# Smart_Cube.net
KiCad netlist of a schematic drawn in Altium Designer
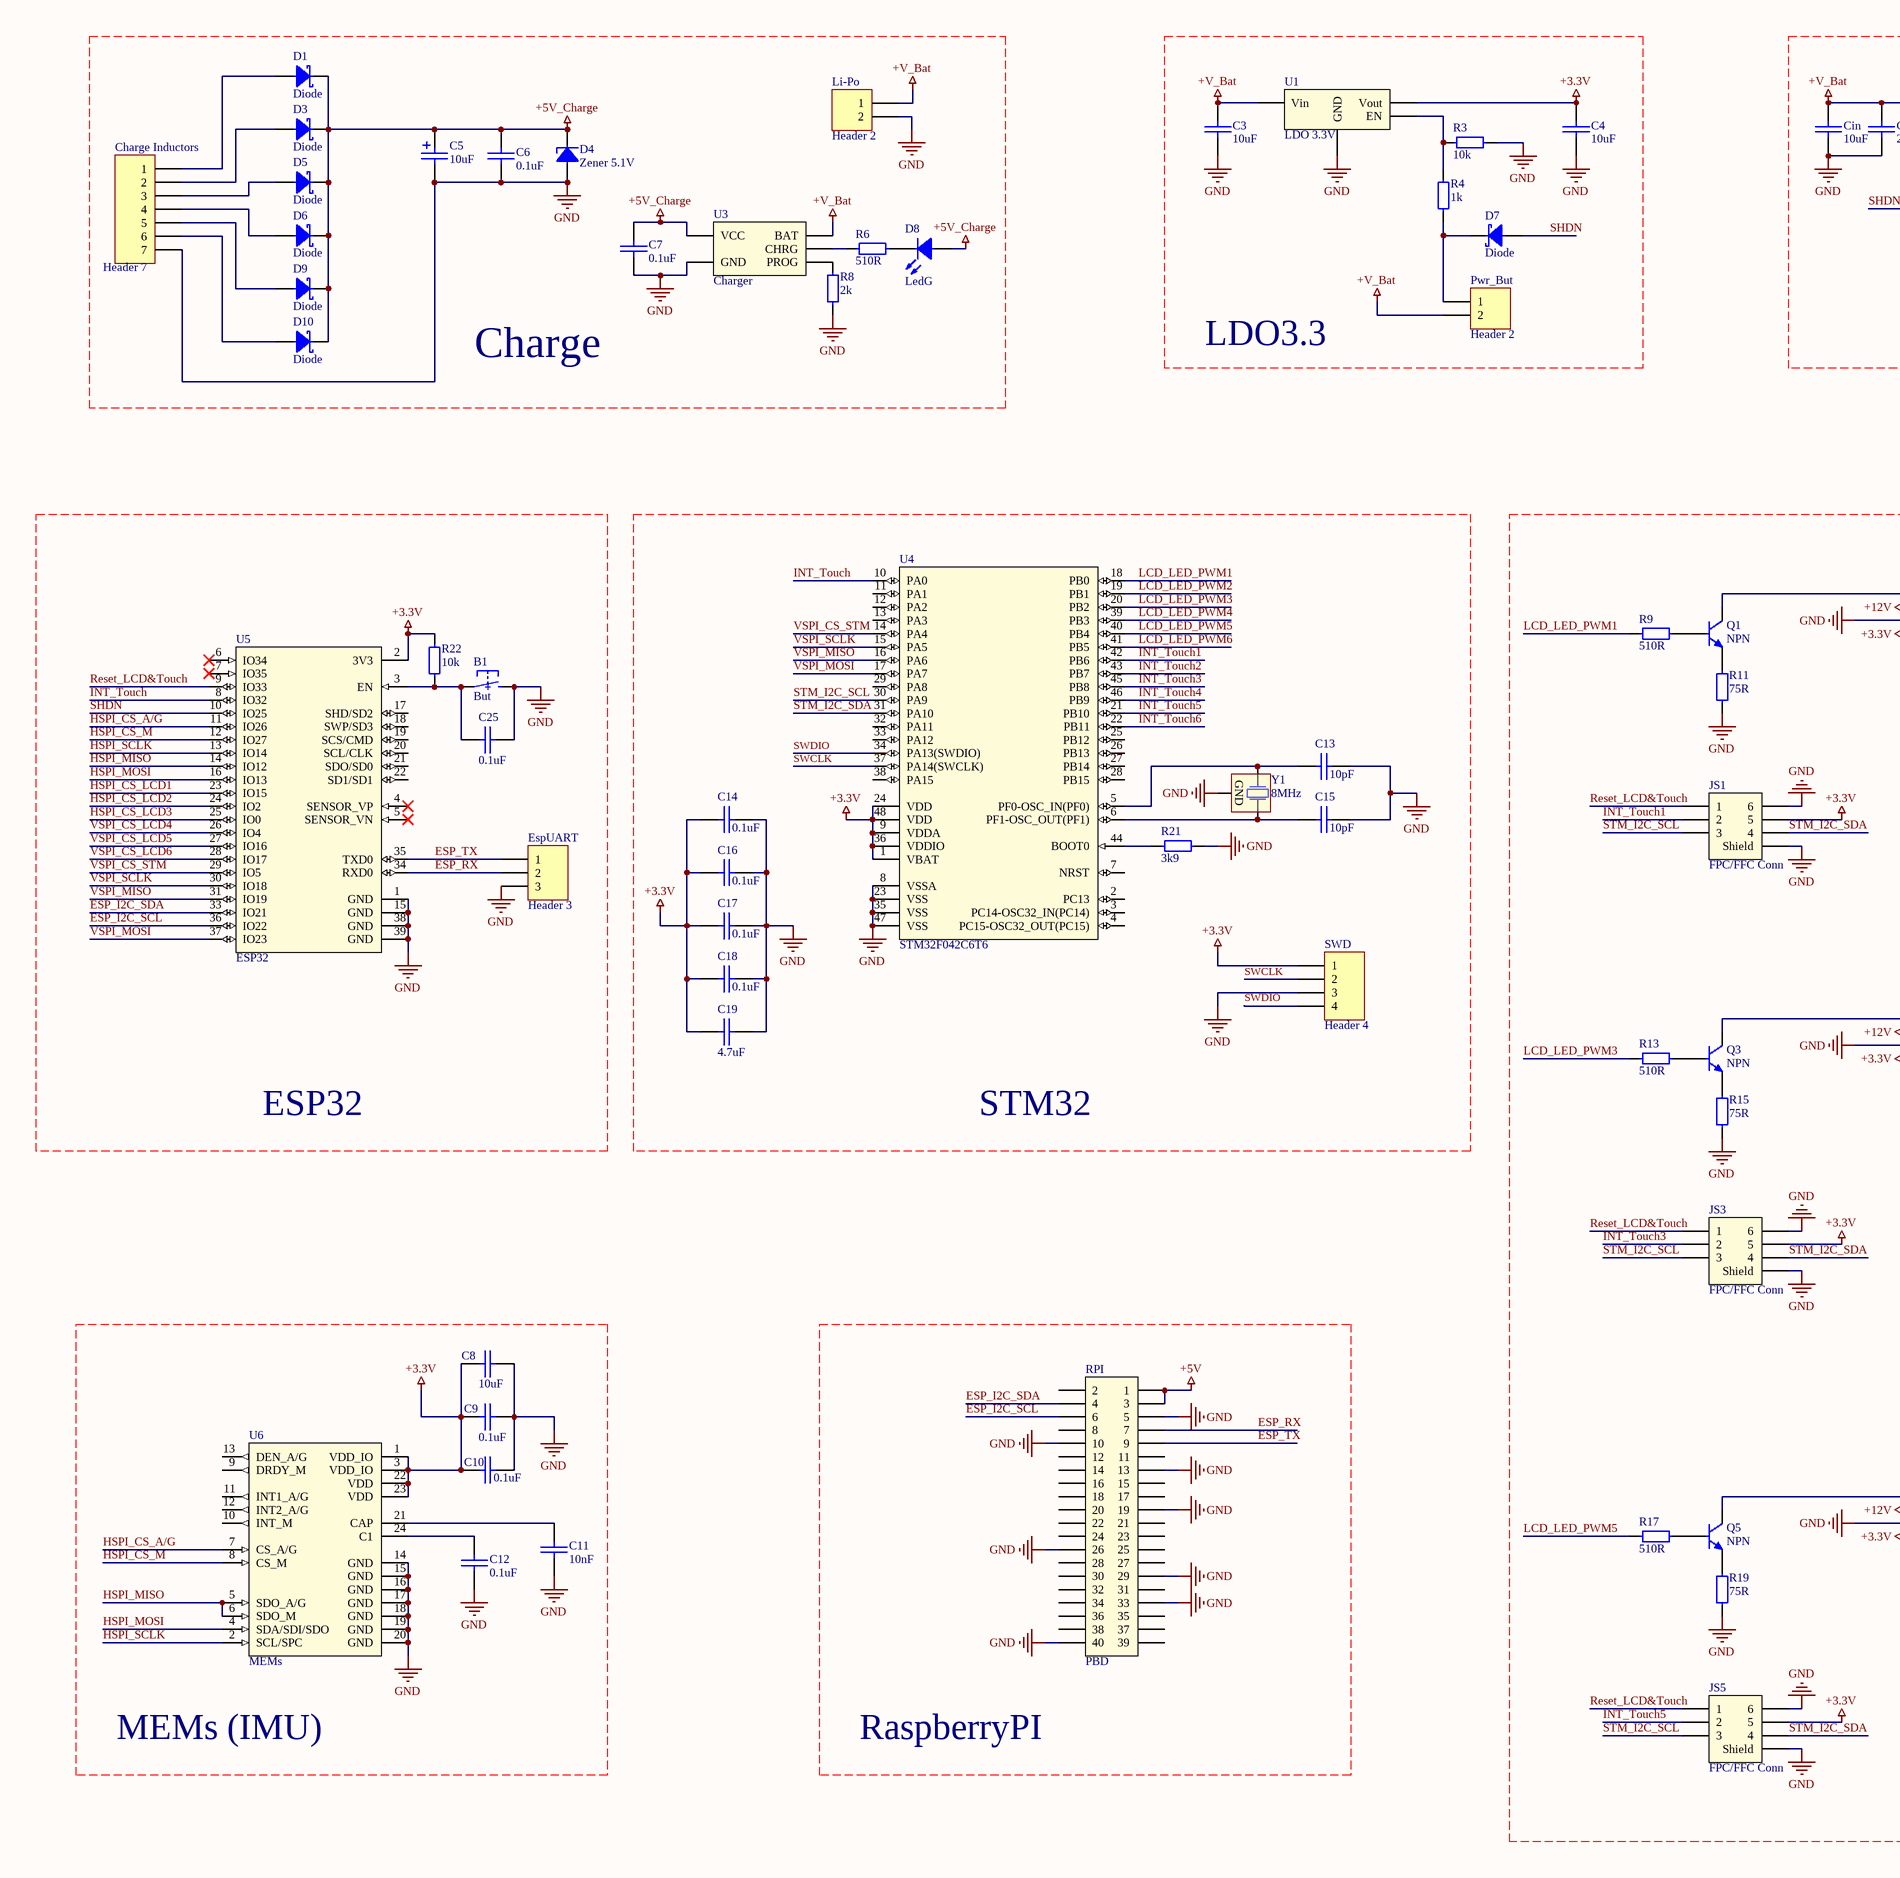
[diagram p0: Smart_Cube.SchDoc, left]
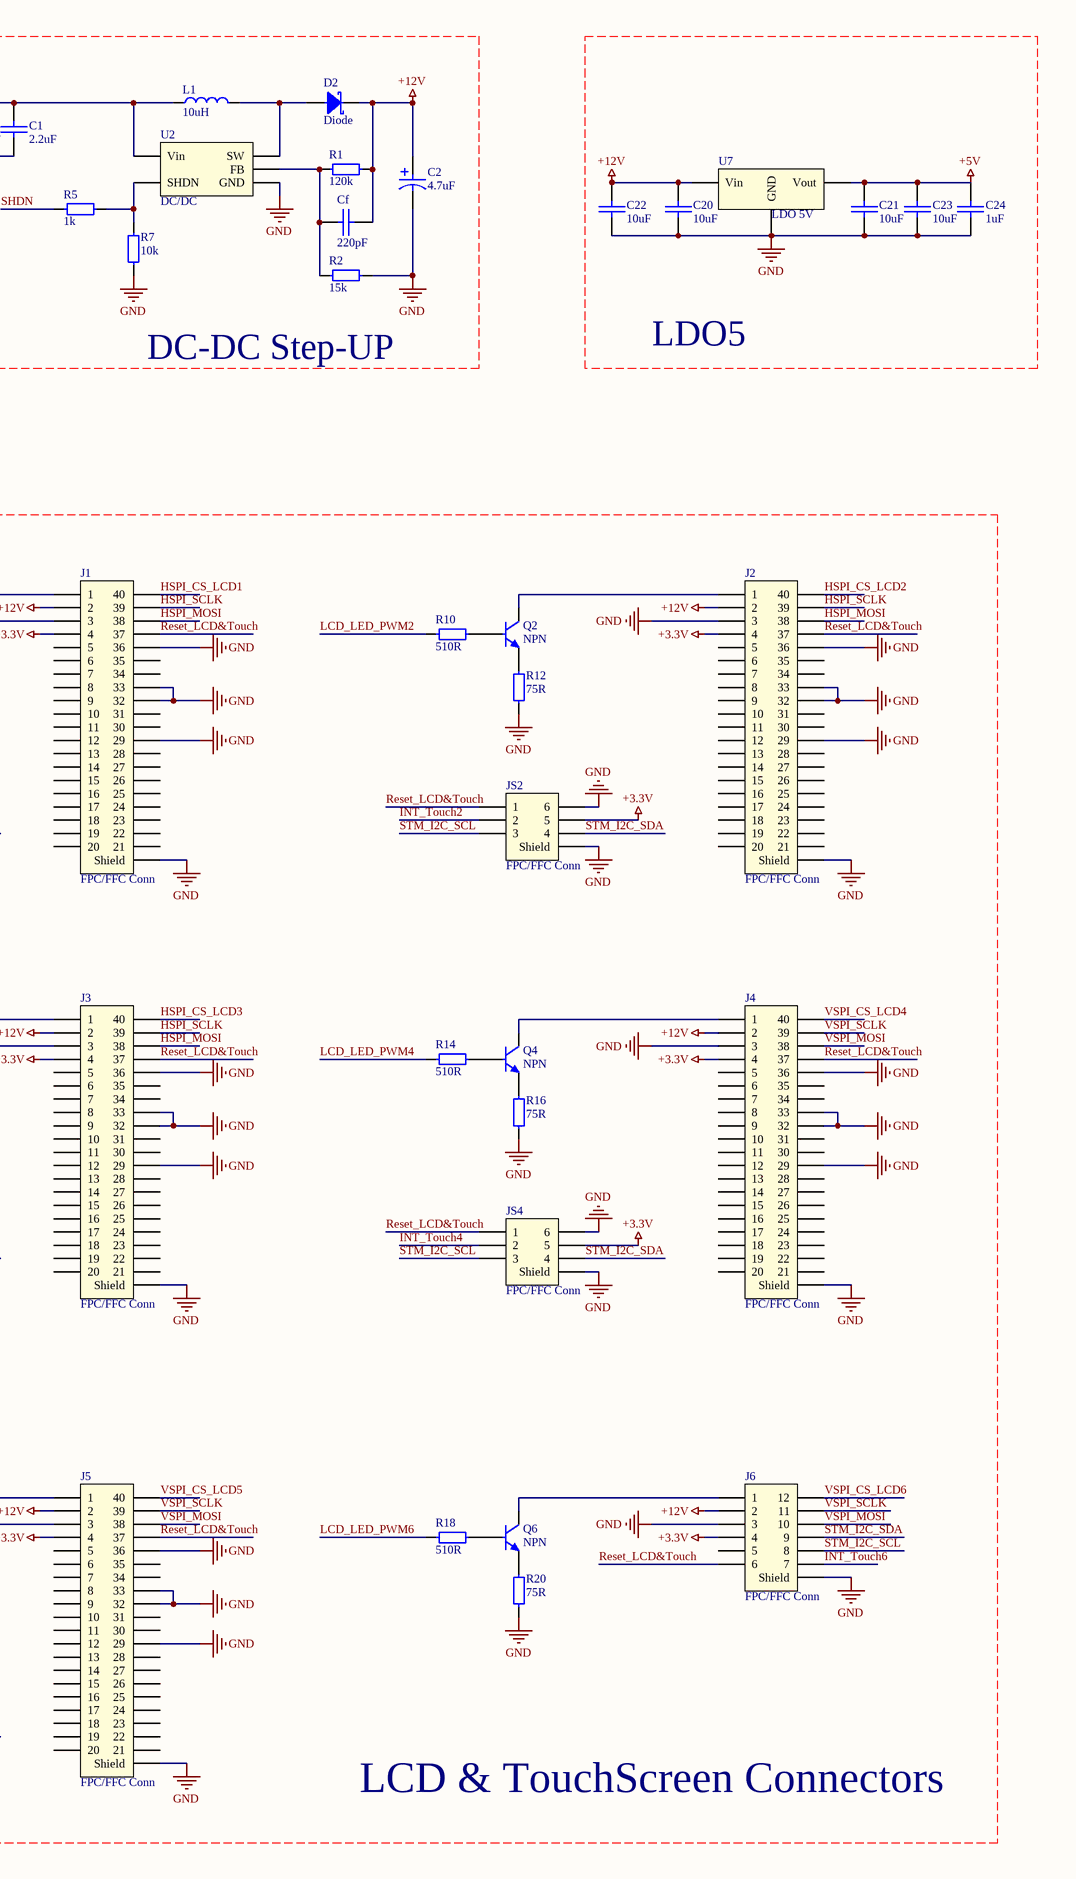
[diagram p1: Smart_Cube.SchDoc, right]

(export (version "E")
  (design (tool "Eeschema 10.0.6"))
  (components
    (comp (ref "B1")
      (value "But")
      (footprint "BUTTON 4x3")
      (description "Button 2 Conn SMD")
      (fields
        (field (name "PART NUMBER") "L-KLS7-TS3608-5.0-180")
        (field (name "MANUFACTURER") "KLS electronic co ltd")
      )
      (libsource (lib "Karen_Components") (part "Button 2 Conn"))
    )
    (comp (ref "C1")
      (value "2.2uF")
      (footprint "0603 Capicator")
      (description "2.2uF X5R 10V 10% 0603")
      (fields
        (field (name "MANUFACTURER") "Murata Manufacturing")
        (field (name "PART NUMBER") "GRM188R61A225KE34D")
      )
      (libsource (lib "Karen_Components") (part "Cap 2.2uF (0603)"))
    )
    (comp (ref "C2")
      (value "4.7uF")
      (footprint "Bar Cap 4x5.4")
      (description "ECAP SMD,  35V, 105°C")
      (fields (field (name "PART NUMBER") "B41121A7475M000") (field (name "MANUFACTURER") "Epcos"))
      (libsource (lib "Karen_Components") (part "Cap Pol 4.7uF"))
    )
    (comp (ref "C3")
      (value "10uF")
      (footprint "0603 Capicator")
      (description "10uF X5R 25V 20% 0603")
      (fields
        (field (name "MANUFACTURER") "Murata Manufacturing")
        (field (name "PART NUMBER") "GRM188R61E106M")
      )
      (libsource (lib "Karen_Components") (part "Cap 10uF (0603)"))
    )
    (comp (ref "C4")
      (value "10uF")
      (footprint "0603 Capicator")
      (description "10uF X5R 25V 20% 0603")
      (fields
        (field (name "MANUFACTURER") "Murata Manufacturing")
        (field (name "PART NUMBER") "GRM188R61E106M")
      )
      (libsource (lib "Karen_Components") (part "Cap 10uF (0603)"))
    )
    (comp (ref "C5")
      (value "10uF")
      (footprint "TANTAL_A_CASE")
      (description "TECAP, 10uF, 16V, case A, 10%")
      (fields (field (name "PART NUMBER") "373033076") (field (name "MANUFACTURER") "China"))
      (libsource (lib "Karen_Components") (part "Cap Tantal 10uF (SMDA)"))
    )
    (comp (ref "C6")
      (value "0.1uF")
      (footprint "0603 Capicator")
      (description "0.1uF X7R 16V 10% 0603")
      (fields
        (field (name "MANUFACTURER") "Murata Manufacturing")
        (field (name "PART NUMBER") "GRM188R71C104KA01D")
      )
      (libsource (lib "Karen_Components") (part "Cap 0.1uF (0603)"))
    )
    (comp (ref "C7")
      (value "0.1uF")
      (footprint "0603 Capicator")
      (description "0.1uF X7R 16V 10% 0603")
      (fields
        (field (name "MANUFACTURER") "Murata Manufacturing")
        (field (name "PART NUMBER") "GRM188R71C104KA01D")
      )
      (libsource (lib "Karen_Components") (part "Cap 0.1uF (0603)"))
    )
    (comp (ref "C8")
      (value "10uF")
      (footprint "0603 Capicator")
      (description "10uF X5R 25V 20% 0603")
      (fields
        (field (name "MANUFACTURER") "Murata Manufacturing")
        (field (name "PART NUMBER") "GRM188R61E106M")
      )
      (libsource (lib "Karen_Components") (part "Cap 10uF (0603)"))
    )
    (comp (ref "C9")
      (value "0.1uF")
      (footprint "0603 Capicator")
      (description "0.1uF X7R 16V 10% 0603")
      (fields
        (field (name "MANUFACTURER") "Murata Manufacturing")
        (field (name "PART NUMBER") "GRM188R71C104KA01D")
      )
      (libsource (lib "Karen_Components") (part "Cap 0.1uF (0603)"))
    )
    (comp (ref "C10")
      (value "0.1uF")
      (footprint "0603 Capicator")
      (description "0.1uF X7R 16V 10% 0603")
      (fields
        (field (name "MANUFACTURER") "Murata Manufacturing")
        (field (name "PART NUMBER") "GRM188R71C104KA01D")
      )
      (libsource (lib "Karen_Components") (part "Cap 0.1uF (0603)"))
    )
    (comp (ref "C11")
      (value "10nF")
      (footprint "0603 Capicator")
      (description "X7R 10nF 100V 10% 0603")
      (fields
        (field (name "MANUFACTURER") "Murata Manufacturing")
        (field (name "PART NUMBER") "GRM188R72A103KA01D")
      )
      (libsource (lib "Karen_Components") (part "Cap 10nF (0603)"))
    )
    (comp (ref "C12")
      (value "0.1uF")
      (footprint "0603 Capicator")
      (description "0.1uF X7R 16V 10% 0603")
      (fields
        (field (name "MANUFACTURER") "Murata Manufacturing")
        (field (name "PART NUMBER") "GRM188R71C104KA01D")
      )
      (libsource (lib "Karen_Components") (part "Cap 0.1uF (0603)"))
    )
    (comp (ref "C13")
      (value "10pF")
      (footprint "0603 Capicator")
      (description "10pF NP0 50V 5% 0603")
      (fields
        (field (name "MANUFACTURER") "Murata Manufacturing")
        (field (name "PART NUMBER") "GRM1885C1H100JA01D")
      )
      (libsource (lib "Karen_Components") (part "Cap 10pF (0603)"))
    )
    (comp (ref "C14")
      (value "0.1uF")
      (footprint "0603 Capicator")
      (description "0.1uF X7R 16V 10% 0603")
      (fields
        (field (name "MANUFACTURER") "Murata Manufacturing")
        (field (name "PART NUMBER") "GRM188R71C104KA01D")
      )
      (libsource (lib "Karen_Components") (part "Cap 0.1uF (0603)"))
    )
    (comp (ref "C15")
      (value "10pF")
      (footprint "0603 Capicator")
      (description "10pF NP0 50V 5% 0603")
      (fields
        (field (name "MANUFACTURER") "Murata Manufacturing")
        (field (name "PART NUMBER") "GRM1885C1H100JA01D")
      )
      (libsource (lib "Karen_Components") (part "Cap 10pF (0603)"))
    )
    (comp (ref "C16")
      (value "0.1uF")
      (footprint "0603 Capicator")
      (description "0.1uF X7R 16V 10% 0603")
      (fields
        (field (name "MANUFACTURER") "Murata Manufacturing")
        (field (name "PART NUMBER") "GRM188R71C104KA01D")
      )
      (libsource (lib "Karen_Components") (part "Cap 0.1uF (0603)"))
    )
    (comp (ref "C17")
      (value "0.1uF")
      (footprint "0603 Capicator")
      (description "0.1uF X7R 16V 10% 0603")
      (fields
        (field (name "MANUFACTURER") "Murata Manufacturing")
        (field (name "PART NUMBER") "GRM188R71C104KA01D")
      )
      (libsource (lib "Karen_Components") (part "Cap 0.1uF (0603)"))
    )
    (comp (ref "C18")
      (value "0.1uF")
      (footprint "0603 Capicator")
      (description "0.1uF X7R 16V 10% 0603")
      (fields
        (field (name "MANUFACTURER") "Murata Manufacturing")
        (field (name "PART NUMBER") "GRM188R71C104KA01D")
      )
      (libsource (lib "Karen_Components") (part "Cap 0.1uF (0603)"))
    )
    (comp (ref "C19")
      (value "4.7uF")
      (footprint "0603 Capicator")
      (description "4.7uF X5R 6.3V 10% 0603")
      (fields
        (field (name "MANUFACTURER") "Murata Manufacturing")
        (field (name "PART NUMBER") "GRM188R60J475KE19D")
      )
      (libsource (lib "Karen_Components") (part "Cap 4.7uF (0603)"))
    )
    (comp (ref "C20")
      (value "10uF")
      (footprint "0603 Capicator")
      (description "10uF X5R 25V 20% 0603")
      (fields
        (field (name "MANUFACTURER") "Murata Manufacturing")
        (field (name "PART NUMBER") "GRM188R61E106M")
      )
      (libsource (lib "Karen_Components") (part "Cap 10uF (0603)"))
    )
    (comp (ref "C21")
      (value "10uF")
      (footprint "0603 Capicator")
      (description "10uF X5R 25V 20% 0603")
      (fields
        (field (name "MANUFACTURER") "Murata Manufacturing")
        (field (name "PART NUMBER") "GRM188R61E106M")
      )
      (libsource (lib "Karen_Components") (part "Cap 10uF (0603)"))
    )
    (comp (ref "C22")
      (value "10uF")
      (footprint "0603 Capicator")
      (description "10uF X5R 25V 20% 0603")
      (fields
        (field (name "MANUFACTURER") "Murata Manufacturing")
        (field (name "PART NUMBER") "GRM188R61E106M")
      )
      (libsource (lib "Karen_Components") (part "Cap 10uF (0603)"))
    )
    (comp (ref "C23")
      (value "10uF")
      (footprint "0603 Capicator")
      (description "10uF X5R 25V 20% 0603")
      (fields
        (field (name "MANUFACTURER") "Murata Manufacturing")
        (field (name "PART NUMBER") "GRM188R61E106M")
      )
      (libsource (lib "Karen_Components") (part "Cap 10uF (0603)"))
    )
    (comp (ref "C24")
      (value "1uF")
      (footprint "0603 Capicator")
      (description "1uF X5R 25V 10% 0603")
      (fields
        (field (name "MANUFACTURER") "Murata Manufacturing")
        (field (name "PART NUMBER") "GRM188R61E105KAADD")
      )
      (libsource (lib "Karen_Components") (part "Cap 1uF (0603)"))
    )
    (comp (ref "C25")
      (value "0.1uF")
      (footprint "0603 Capicator")
      (description "0.1uF X7R 16V 10% 0603")
      (fields
        (field (name "MANUFACTURER") "Murata Manufacturing")
        (field (name "PART NUMBER") "GRM188R71C104KA01D")
      )
      (libsource (lib "Karen_Components") (part "Cap 0.1uF (0603)"))
    )
    (comp (ref "Cf")
      (value "220pF")
      (footprint "0603 Capicator")
      (description "220pF NP0 50V 5% 0603")
      (fields
        (field (name "MANUFACTURER") "Murata Manufacturing")
        (field (name "PART NUMBER") "GRM1885C1H221J")
      )
      (libsource (lib "Karen_Components") (part "Cap 220pF (0603)"))
    )
    (comp (ref "Charge Inductors")
      (value "Header 7")
      (footprint "HDR1X7")
      (description "Header, 7-Pin")
      (fields (field (name "PUBLISHER") "Altium Limited"))
      (libsource (lib "Miscellaneous Connectors") (part "Header 7"))
    )
    (comp (ref "Cin")
      (value "10uF")
      (footprint "0603 Capicator")
      (description "10uF X5R 25V 20% 0603")
      (fields
        (field (name "MANUFACTURER") "Murata Manufacturing")
        (field (name "PART NUMBER") "GRM188R61E106M")
      )
      (libsource (lib "Karen_Components") (part "Cap 10uF (0603)"))
    )
    (comp (ref "D1")
      (value "Diode")
      (footprint "sod-123")
      (description "0.5 A, Low Forward Voltage less than 385 mV, 400 mW Power Dissipation Package")
      (fields (field (name "PART NUMBER") "MBR0520L") (field (name "MANUFACTURER") "ON Semiconductor"))
      (libsource (lib "Karen_Components") (part "Diode Schottky (SOD-123)"))
    )
    (comp (ref "D2")
      (value "Diode")
      (footprint "sod-123")
      (description "0.5 A, Low Forward Voltage less than 385 mV, 400 mW Power Dissipation Package")
      (fields (field (name "PART NUMBER") "MBR0520L") (field (name "MANUFACTURER") "ON Semiconductor"))
      (libsource (lib "Karen_Components") (part "Diode Schottky (SOD-123)"))
    )
    (comp (ref "D3")
      (value "Diode")
      (footprint "sod-123")
      (description "0.5 A, Low Forward Voltage less than 385 mV, 400 mW Power Dissipation Package")
      (fields (field (name "PART NUMBER") "MBR0520L") (field (name "MANUFACTURER") "ON Semiconductor"))
      (libsource (lib "Karen_Components") (part "Diode Schottky (SOD-123)"))
    )
    (comp (ref "D4")
      (value "Zener 5.1V")
      (footprint "sod-323")
      (description "300mW")
      (fields (field (name "PART NUMBER") "BZX384-C5V1,115") (field (name "MANUFACTURER") "Nexperia"))
      (libsource (lib "Karen_Components") (part "Zener Diode 5.1V"))
    )
    (comp (ref "D5")
      (value "Diode")
      (footprint "sod-123")
      (description "0.5 A, Low Forward Voltage less than 385 mV, 400 mW Power Dissipation Package")
      (fields (field (name "PART NUMBER") "MBR0520L") (field (name "MANUFACTURER") "ON Semiconductor"))
      (libsource (lib "Karen_Components") (part "Diode Schottky (SOD-123)"))
    )
    (comp (ref "D6")
      (value "Diode")
      (footprint "sod-123")
      (description "0.5 A, Low Forward Voltage less than 385 mV, 400 mW Power Dissipation Package")
      (fields (field (name "PART NUMBER") "MBR0520L") (field (name "MANUFACTURER") "ON Semiconductor"))
      (libsource (lib "Karen_Components") (part "Diode Schottky (SOD-123)"))
    )
    (comp (ref "D7")
      (value "Diode")
      (footprint "sod-123")
      (description "0.5 A, Low Forward Voltage less than 385 mV, 400 mW Power Dissipation Package")
      (fields (field (name "PART NUMBER") "MBR0520L") (field (name "MANUFACTURER") "ON Semiconductor"))
      (libsource (lib "Karen_Components") (part "Diode Schottky (SOD-123)"))
    )
    (comp (ref "D8")
      (value "LedG")
      (footprint "0805 LED")
      (description "Led Green SMD 1608, 120°, 525nM")
      (fields
        (field (name "PART NUMBER") "TO-1608BC-PG")
        (field (name "MANUFACTURER") "Taiwan Oasis Technology")
      )
      (libsource (lib "Karen_Components") (part "Led Green"))
    )
    (comp (ref "D9")
      (value "Diode")
      (footprint "sod-123")
      (description "0.5 A, Low Forward Voltage less than 385 mV, 400 mW Power Dissipation Package")
      (fields (field (name "PART NUMBER") "MBR0520L") (field (name "MANUFACTURER") "ON Semiconductor"))
      (libsource (lib "Karen_Components") (part "Diode Schottky (SOD-123)"))
    )
    (comp (ref "D10")
      (value "Diode")
      (footprint "sod-123")
      (description "0.5 A, Low Forward Voltage less than 385 mV, 400 mW Power Dissipation Package")
      (fields (field (name "PART NUMBER") "MBR0520L") (field (name "MANUFACTURER") "ON Semiconductor"))
      (libsource (lib "Karen_Components") (part "Diode Schottky (SOD-123)"))
    )
    (comp (ref "EspUART")
      (value "Header 3")
      (footprint "HDR1X3")
      (description "Header, 3-Pin")
      (fields (field (name "PUBLISHER") "Altium Limited"))
      (libsource (lib "Miscellaneous Connectors") (part "Header 3"))
    )
    (comp (ref "J1")
      (value "FPC/FFC Conn")
      (footprint "FH12-40S Vertical")
      (description "Connector to Display's trail")
      (fields
        (field (name "PART NUMBER") "FH12-40S-0.5SVA(54)")
        (field (name "MANUFACTURER") "Hirose Electric")
      )
      (libsource (lib "Karen_Components") (part "Conn40x1 (FH12 Vertical)"))
    )
    (comp (ref "J2")
      (value "FPC/FFC Conn")
      (footprint "FH12-40S Vertical")
      (description "Connector to Display's trail")
      (fields
        (field (name "PART NUMBER") "FH12-40S-0.5SVA(54)")
        (field (name "MANUFACTURER") "Hirose Electric")
      )
      (libsource (lib "Karen_Components") (part "Conn40x1 (FH12 Vertical)"))
    )
    (comp (ref "J3")
      (value "FPC/FFC Conn")
      (footprint "FH12-40S Vertical")
      (description "Connector to Display's trail")
      (fields
        (field (name "PART NUMBER") "FH12-40S-0.5SVA(54)")
        (field (name "MANUFACTURER") "Hirose Electric")
      )
      (libsource (lib "Karen_Components") (part "Conn40x1 (FH12 Vertical)"))
    )
    (comp (ref "J4")
      (value "FPC/FFC Conn")
      (footprint "FH12-40S Vertical")
      (description "Connector to Display's trail")
      (fields
        (field (name "PART NUMBER") "FH12-40S-0.5SVA(54)")
        (field (name "MANUFACTURER") "Hirose Electric")
      )
      (libsource (lib "Karen_Components") (part "Conn40x1 (FH12 Vertical)"))
    )
    (comp (ref "J5")
      (value "FPC/FFC Conn")
      (footprint "FH12-40S Vertical")
      (description "Connector to Display's trail")
      (fields
        (field (name "PART NUMBER") "FH12-40S-0.5SVA(54)")
        (field (name "MANUFACTURER") "Hirose Electric")
      )
      (libsource (lib "Karen_Components") (part "Conn40x1 (FH12 Vertical)"))
    )
    (comp (ref "J6")
      (value "FPC/FFC Conn")
      (footprint "FH12-12S Vertical")
      (description "Connector to trail")
      (fields
        (field (name "PART NUMBER") "FH12-12S-0.5SVA(54)")
        (field (name "MANUFACTURER") "Hirose Electric")
      )
      (libsource (lib "Karen_Components") (part "Conn12x1 (FH12 Vertical)"))
    )
    (comp (ref "JS1")
      (value "FPC/FFC Conn")
      (footprint "FH12-6s Vertical")
      (description "Connector to touch sensor's trail")
      (fields
        (field (name "PART NUMBER") "FH12-6S-0.5SVA(54)")
        (field (name "MANUFACTURER") "Hirose Electric")
      )
      (libsource (lib "Karen_Components") (part "Conn6x1 (FH12 Vertical)"))
    )
    (comp (ref "JS2")
      (value "FPC/FFC Conn")
      (footprint "FH12-6s Vertical")
      (description "Connector to touch sensor's trail")
      (fields
        (field (name "PART NUMBER") "FH12-6S-0.5SVA(54)")
        (field (name "MANUFACTURER") "Hirose Electric")
      )
      (libsource (lib "Karen_Components") (part "Conn6x1 (FH12 Vertical)"))
    )
    (comp (ref "JS3")
      (value "FPC/FFC Conn")
      (footprint "FH12-6s Vertical")
      (description "Connector to touch sensor's trail")
      (fields
        (field (name "PART NUMBER") "FH12-6S-0.5SVA(54)")
        (field (name "MANUFACTURER") "Hirose Electric")
      )
      (libsource (lib "Karen_Components") (part "Conn6x1 (FH12 Vertical)"))
    )
    (comp (ref "JS4")
      (value "FPC/FFC Conn")
      (footprint "FH12-6s Vertical")
      (description "Connector to touch sensor's trail")
      (fields
        (field (name "PART NUMBER") "FH12-6S-0.5SVA(54)")
        (field (name "MANUFACTURER") "Hirose Electric")
      )
      (libsource (lib "Karen_Components") (part "Conn6x1 (FH12 Vertical)"))
    )
    (comp (ref "JS5")
      (value "FPC/FFC Conn")
      (footprint "FH12-6s Vertical")
      (description "Connector to touch sensor's trail")
      (fields
        (field (name "PART NUMBER") "FH12-6S-0.5SVA(54)")
        (field (name "MANUFACTURER") "Hirose Electric")
      )
      (libsource (lib "Karen_Components") (part "Conn6x1 (FH12 Vertical)"))
    )
    (comp (ref "L1")
      (value "10uH")
      (footprint "SDR")
      (description "10uH, D=5.8mm, 1450mA")
      (fields (field (name "PART NUMBER") "SDR0604-100ML") (field (name "MANUFACTURER") "Bourns"))
      (libsource (lib "Karen_Components") (part "Inductor 10uH (1.5A)"))
    )
    (comp (ref "Li-Po")
      (value "Header 2")
      (footprint "HDR1X2")
      (description "Header, 2-Pin")
      (fields (field (name "PUBLISHER") "Altium Limited"))
      (libsource (lib "") (part "Header 2_1"))
    )
    (comp (ref "Pwr_But")
      (value "Header 2")
      (footprint "HDR1X2")
      (description "Header, 2-Pin")
      (fields (field (name "PUBLISHER") "Altium Limited"))
      (libsource (lib "Miscellaneous Connectors") (part "Header 2"))
    )
    (comp (ref "Q1")
      (value "NPN")
      (footprint "SOT-23")
      (description "NPN general-purpose transistors")
      (fields (field (name "PART NUMBER") "BC817-40,215") (field (name "MANUFACTURER") "Nexperia"))
      (libsource (lib "Karen_Components") (part "NPN [BC817]"))
    )
    (comp (ref "Q2")
      (value "NPN")
      (footprint "SOT-23")
      (description "NPN general-purpose transistors")
      (fields (field (name "PART NUMBER") "BC817-40,215") (field (name "MANUFACTURER") "Nexperia"))
      (libsource (lib "Karen_Components") (part "NPN [BC817]"))
    )
    (comp (ref "Q3")
      (value "NPN")
      (footprint "SOT-23")
      (description "NPN general-purpose transistors")
      (fields (field (name "PART NUMBER") "BC817-40,215") (field (name "MANUFACTURER") "Nexperia"))
      (libsource (lib "Karen_Components") (part "NPN [BC817]"))
    )
    (comp (ref "Q4")
      (value "NPN")
      (footprint "SOT-23")
      (description "NPN general-purpose transistors")
      (fields (field (name "PART NUMBER") "BC817-40,215") (field (name "MANUFACTURER") "Nexperia"))
      (libsource (lib "Karen_Components") (part "NPN [BC817]"))
    )
    (comp (ref "Q5")
      (value "NPN")
      (footprint "SOT-23")
      (description "NPN general-purpose transistors")
      (fields (field (name "PART NUMBER") "BC817-40,215") (field (name "MANUFACTURER") "Nexperia"))
      (libsource (lib "Karen_Components") (part "NPN [BC817]"))
    )
    (comp (ref "Q6")
      (value "NPN")
      (footprint "SOT-23")
      (description "NPN general-purpose transistors")
      (fields (field (name "PART NUMBER") "BC817-40,215") (field (name "MANUFACTURER") "Nexperia"))
      (libsource (lib "Karen_Components") (part "NPN [BC817]"))
    )
    (comp (ref "R1")
      (value "120k")
      (footprint "0603 Resistor")
      (description "0.1W 0603 120k, 1%")
      (fields (field (name "PART NUMBER") "RC0603FR-07120KL") (field (name "MANUFACTURER") "Taiwan"))
      (libsource (lib "Karen_Components") (part "Res 120k (0603)"))
    )
    (comp (ref "R2")
      (value "15k")
      (footprint "0603 Resistor")
      (description "0.1W 0603 15k, 1%")
      (fields (field (name "PART NUMBER") "RC0603FR-0715KL") (field (name "MANUFACTURER") "Taiwan"))
      (libsource (lib "Karen_Components") (part "Res 15k (0603)"))
    )
    (comp (ref "R3")
      (value "10k")
      (footprint "0603 Resistor")
      (description "0.1W 0603 10k, 1%")
      (fields (field (name "PART NUMBER") "RC0603FR-0710KL") (field (name "MANUFACTURER") "Taiwan"))
      (libsource (lib "Karen_Components") (part "Res 10k (0603)"))
    )
    (comp (ref "R4")
      (value "1k")
      (footprint "0603 Resistor")
      (description "0.1W 0603 1k, 1%")
      (fields (field (name "PART NUMBER") "RC0603FR-071KL") (field (name "MANUFACTURER") "Taiwan"))
      (libsource (lib "Karen_Components") (part "Res 1k (0603)"))
    )
    (comp (ref "R5")
      (value "1k")
      (footprint "0603 Resistor")
      (description "0.1W 0603 1k, 1%")
      (fields (field (name "PART NUMBER") "RC0603FR-071KL") (field (name "MANUFACTURER") "Taiwan"))
      (libsource (lib "Karen_Components") (part "Res 1k (0603)"))
    )
    (comp (ref "R6")
      (value "510R")
      (footprint "0603 Resistor")
      (description "0.1W 0603 510R, 1%")
      (fields (field (name "PART NUMBER") "RC0603FR-07510RL") (field (name "MANUFACTURER") "Taiwan"))
      (libsource (lib "Karen_Components") (part "Res 510R (0603)"))
    )
    (comp (ref "R7")
      (value "10k")
      (footprint "0603 Resistor")
      (description "0.1W 0603 10k, 1%")
      (fields (field (name "PART NUMBER") "RC0603FR-0710KL") (field (name "MANUFACTURER") "Taiwan"))
      (libsource (lib "Karen_Components") (part "Res 10k (0603)"))
    )
    (comp (ref "R8")
      (value "2k")
      (footprint "0603 Resistor")
      (description "0.1W 0603 2k, 1%")
      (fields (field (name "PART NUMBER") "RC0603FR-072KL") (field (name "MANUFACTURER") "Taiwan"))
      (libsource (lib "Karen_Components") (part "Res 2k (0603)"))
    )
    (comp (ref "R9")
      (value "510R")
      (footprint "0603 Resistor")
      (description "0.1W 0603 510R, 1%")
      (fields (field (name "PART NUMBER") "RC0603FR-07510RL") (field (name "MANUFACTURER") "Taiwan"))
      (libsource (lib "Karen_Components") (part "Res 510R (0603)"))
    )
    (comp (ref "R10")
      (value "510R")
      (footprint "0603 Resistor")
      (description "0.1W 0603 510R, 1%")
      (fields (field (name "PART NUMBER") "RC0603FR-07510RL") (field (name "MANUFACTURER") "Taiwan"))
      (libsource (lib "Karen_Components") (part "Res 510R (0603)"))
    )
    (comp (ref "R11")
      (value "75R")
      (footprint "0603 Resistor")
      (description "0.1W 0603 75R, 1%")
      (fields (field (name "PART NUMBER") "RC0603FR-0775RL") (field (name "MANUFACTURER") "Taiwan"))
      (libsource (lib "Karen_Components") (part "Res 75R (0603)"))
    )
    (comp (ref "R12")
      (value "75R")
      (footprint "0603 Resistor")
      (description "0.1W 0603 75R, 1%")
      (fields (field (name "PART NUMBER") "RC0603FR-0775RL") (field (name "MANUFACTURER") "Taiwan"))
      (libsource (lib "Karen_Components") (part "Res 75R (0603)"))
    )
    (comp (ref "R13")
      (value "510R")
      (footprint "0603 Resistor")
      (description "0.1W 0603 510R, 1%")
      (fields (field (name "PART NUMBER") "RC0603FR-07510RL") (field (name "MANUFACTURER") "Taiwan"))
      (libsource (lib "Karen_Components") (part "Res 510R (0603)"))
    )
    (comp (ref "R14")
      (value "510R")
      (footprint "0603 Resistor")
      (description "0.1W 0603 510R, 1%")
      (fields (field (name "PART NUMBER") "RC0603FR-07510RL") (field (name "MANUFACTURER") "Taiwan"))
      (libsource (lib "Karen_Components") (part "Res 510R (0603)"))
    )
    (comp (ref "R15")
      (value "75R")
      (footprint "0603 Resistor")
      (description "0.1W 0603 75R, 1%")
      (fields (field (name "PART NUMBER") "RC0603FR-0775RL") (field (name "MANUFACTURER") "Taiwan"))
      (libsource (lib "Karen_Components") (part "Res 75R (0603)"))
    )
    (comp (ref "R16")
      (value "75R")
      (footprint "0603 Resistor")
      (description "0.1W 0603 75R, 1%")
      (fields (field (name "PART NUMBER") "RC0603FR-0775RL") (field (name "MANUFACTURER") "Taiwan"))
      (libsource (lib "Karen_Components") (part "Res 75R (0603)"))
    )
    (comp (ref "R17")
      (value "510R")
      (footprint "0603 Resistor")
      (description "0.1W 0603 510R, 1%")
      (fields (field (name "PART NUMBER") "RC0603FR-07510RL") (field (name "MANUFACTURER") "Taiwan"))
      (libsource (lib "Karen_Components") (part "Res 510R (0603)"))
    )
    (comp (ref "R18")
      (value "510R")
      (footprint "0603 Resistor")
      (description "0.1W 0603 510R, 1%")
      (fields (field (name "PART NUMBER") "RC0603FR-07510RL") (field (name "MANUFACTURER") "Taiwan"))
      (libsource (lib "Karen_Components") (part "Res 510R (0603)"))
    )
    (comp (ref "R19")
      (value "75R")
      (footprint "0603 Resistor")
      (description "0.1W 0603 75R, 1%")
      (fields (field (name "PART NUMBER") "RC0603FR-0775RL") (field (name "MANUFACTURER") "Taiwan"))
      (libsource (lib "Karen_Components") (part "Res 75R (0603)"))
    )
    (comp (ref "R20")
      (value "75R")
      (footprint "0603 Resistor")
      (description "0.1W 0603 75R, 1%")
      (fields (field (name "PART NUMBER") "RC0603FR-0775RL") (field (name "MANUFACTURER") "Taiwan"))
      (libsource (lib "Karen_Components") (part "Res 75R (0603)"))
    )
    (comp (ref "R21")
      (value "3k9")
      (footprint "0603 Resistor")
      (description "0.1W 0603 3.9k, 1%")
      (fields (field (name "PART NUMBER") "RC0603FR-073K9L") (field (name "MANUFACTURER") "Taiwan"))
      (libsource (lib "Karen_Components") (part "Res 3.9k (0603)"))
    )
    (comp (ref "R22")
      (value "10k")
      (footprint "0603 Resistor")
      (description "0.1W 0603 10k, 1%")
      (fields (field (name "PART NUMBER") "RC0603FR-0710KL") (field (name "MANUFACTURER") "Taiwan"))
      (libsource (lib "Karen_Components") (part "Res 10k (0603)"))
    )
    (comp (ref "RPI")
      (value "PBD")
      (footprint "PBD 2x20")
      (description "Female for PLD")
      (fields
        (field (name "PART NUMBER") "DS1023-2*20S21")
        (field (name "MANUFACTURER") "Ningbo connfly electronic")
      )
      (libsource (lib "Karen_Components") (part "Conn20x2 (PBD)"))
    )
    (comp (ref "SWD")
      (value "Header 4")
      (footprint "HDR1X4")
      (description "Header, 4-Pin")
      (fields (field (name "PUBLISHER") "Altium Limited"))
      (libsource (lib "Miscellaneous Connectors") (part "Header 4"))
    )
    (comp (ref "U1")
      (value "LDO 3.3V")
      (footprint "SOT-23-5")
      (fields (field (name "PART NUMBER") "LM8805SF5-3.3") (field (name "MANUFACTURER") "TAEJIN TECHNOLOGY"))
      (libsource (lib "Karen_Components") (part "LDO 3.3V [LM]"))
    )
    (comp (ref "U2")
      (value "DC/DC")
      (footprint "SOT-23-5")
      (fields (field (name "MANUFACTURER") "Texas Instruments") (field (name "PART NUMBER") "LM2731YMF/NOPB"))
      (libsource (lib "Karen_Components") (part "DC/DC Controller [LM2731]"))
    )
    (comp (ref "U3")
      (value "Charger")
      (footprint "SOT-23-5")
      (fields
        (field (name "PART NUMBER") "LTC4054ES5-4.2#PBF")
        (field (name "MANUFACTURER") "Linear Technology")
      )
      (libsource (lib "Karen_Components") (part "Charger [LTC]"))
    )
    (comp (ref "U4")
      (value "STM32F042C6T6")
      (footprint "LQFP48")
      (fields (field (name "MANUFACTURER") "STMicroelectronics"))
      (libsource (lib "Karen_Components") (part "STM32F042C6T6"))
    )
    (comp (ref "U5")
      (value "ESP32")
      (footprint "ESP32-WROOM-32U")
      (fields
        (field (name "PART NUMBER") "ESP32-WROOM-32U (16MB)")
        (field (name "MANUFACTURER") "Espressif Systems")
      )
      (libsource (lib "Karen_Components") (part "ESP32-WROOM (D0WD)"))
    )
    (comp (ref "U6")
      (value "MEMs")
      (footprint "LGA 3.5x3x1 mm 24-lead")
      (fields (field (name "MANUFACTURER") "STMicroelectronics") (field (name "PART NUMBER") "LSM9DS1TR"))
      (libsource (lib "Karen_Components") (part "MEMs 9 Axis"))
    )
    (comp (ref "U7")
      (value "LDO 5V")
      (footprint "SOT-223")
      (description "A low dropout Linear Regulator with a dropout of 5V at 800mA of load current")
      (fields
        (field (name "PART NUMBER") "LM1117IMPX-5.0/NOPB")
        (field (name "MANUFACTURER") "Texas Instruments")
      )
      (libsource (lib "Karen_Components") (part "LDO 5V [LM]"))
    )
    (comp (ref "Y1")
      (value "8MHz")
      (footprint "Crystal ABM")
      (description "8.0MHz 10pf 10ppm -10C +60C")
      (fields (field (name "MANUFACTURER") "ABRACON") (field (name "PART NUMBER") "ABM3B-8.000MHZ-10-1UT"))
      (libsource (lib "Karen_Components") (part "Crystal 8MHz [ABM]"))
    )
  )
  (nets
    (net (code "1") (name "+3.3V") (class "Default")
      (node (ref "C10") (pin "1") (pinfunction "1_1") (pintype "passive"))
      (node (ref "C14") (pin "1") (pinfunction "1_1") (pintype "passive"))
      (node (ref "C16") (pin "1") (pinfunction "1_1") (pintype "passive"))
      (node (ref "C17") (pin "1") (pinfunction "1_1") (pintype "passive"))
      (node (ref "C18") (pin "1") (pinfunction "1_1") (pintype "passive"))
      (node (ref "C19") (pin "1") (pinfunction "1_1") (pintype "passive"))
      (node (ref "C4") (pin "2") (pinfunction "2_2") (pintype "passive"))
      (node (ref "C8") (pin "1") (pinfunction "1_1") (pintype "passive"))
      (node (ref "C9") (pin "1") (pinfunction "1_1") (pintype "passive"))
      (node (ref "J1") (pin "4") (pinfunction "4_4") (pintype "passive"))
      (node (ref "J2") (pin "4") (pinfunction "4_4") (pintype "passive"))
      (node (ref "J3") (pin "4") (pinfunction "4_4") (pintype "passive"))
      (node (ref "J4") (pin "4") (pinfunction "4_4") (pintype "passive"))
      (node (ref "J5") (pin "4") (pinfunction "4_4") (pintype "passive"))
      (node (ref "J6") (pin "4") (pinfunction "4_4") (pintype "passive"))
      (node (ref "JS1") (pin "5") (pinfunction "5_5") (pintype "passive"))
      (node (ref "JS2") (pin "5") (pinfunction "5_5") (pintype "passive"))
      (node (ref "JS3") (pin "5") (pinfunction "5_5") (pintype "passive"))
      (node (ref "JS4") (pin "5") (pinfunction "5_5") (pintype "passive"))
      (node (ref "JS5") (pin "5") (pinfunction "5_5") (pintype "passive"))
      (node (ref "R22") (pin "2") (pinfunction "2_2") (pintype "passive"))
      (node (ref "SWD") (pin "1") (pinfunction "1_1") (pintype "passive"))
      (node (ref "U1") (pin "5") (pinfunction "Vout_5") (pintype "power_in"))
      (node (ref "U4") (pin "1") (pinfunction "VBAT_1") (pintype "power_in"))
      (node (ref "U4") (pin "24") (pinfunction "VDD_24") (pintype "power_in"))
      (node (ref "U4") (pin "36") (pinfunction "VDDIO_36") (pintype "power_in"))
      (node (ref "U4") (pin "48") (pinfunction "VDD_48") (pintype "power_in"))
      (node (ref "U4") (pin "9") (pinfunction "VDDA_9") (pintype "power_in"))
      (node (ref "U5") (pin "2") (pinfunction "3V3_2") (pintype "power_in"))
      (node (ref "U6") (pin "1") (pinfunction "VDD_IO_1") (pintype "power_in"))
      (node (ref "U6") (pin "22") (pinfunction "VDD_22") (pintype "power_in"))
      (node (ref "U6") (pin "23") (pinfunction "VDD_23") (pintype "power_in"))
      (node (ref "U6") (pin "3") (pinfunction "VDD_IO_3") (pintype "power_in"))
    )
    (net (code "2") (name "+5V") (class "Default")
      (node (ref "C21") (pin "2") (pinfunction "2_2") (pintype "passive"))
      (node (ref "C23") (pin "2") (pinfunction "2_2") (pintype "passive"))
      (node (ref "C24") (pin "2") (pinfunction "2_2") (pintype "passive"))
      (node (ref "RPI") (pin "1") (pinfunction "1_1") (pintype "passive"))
      (node (ref "RPI") (pin "3") (pinfunction "3_3") (pintype "passive"))
      (node (ref "U7") (pin "2") (pinfunction "Vout_2") (pintype "power_in"))
    )
    (net (code "3") (name "+5V_Charge") (class "Default")
      (node (ref "C5") (pin "2") (pinfunction "2_2") (pintype "passive"))
      (node (ref "C6") (pin "2") (pinfunction "2_2") (pintype "passive"))
      (node (ref "C7") (pin "2") (pinfunction "2_2") (pintype "passive"))
      (node (ref "D1") (pin "2") (pinfunction "2_2") (pintype "passive"))
      (node (ref "D10") (pin "2") (pinfunction "2_2") (pintype "passive"))
      (node (ref "D3") (pin "2") (pinfunction "2_2") (pintype "passive"))
      (node (ref "D4") (pin "2") (pinfunction "2_2") (pintype "passive"))
      (node (ref "D5") (pin "2") (pinfunction "2_2") (pintype "passive"))
      (node (ref "D6") (pin "2") (pinfunction "2_2") (pintype "passive"))
      (node (ref "D8") (pin "1") (pinfunction "1_1") (pintype "passive"))
      (node (ref "D9") (pin "2") (pinfunction "2_2") (pintype "passive"))
      (node (ref "U3") (pin "4") (pinfunction "VCC_4") (pintype "power_in"))
    )
    (net (code "4") (name "+12V") (class "Default")
      (node (ref "C2") (pin "2") (pinfunction "2_2") (pintype "passive"))
      (node (ref "C20") (pin "2") (pinfunction "2_2") (pintype "passive"))
      (node (ref "C22") (pin "2") (pinfunction "2_2") (pintype "passive"))
      (node (ref "Cf") (pin "2") (pinfunction "2_2") (pintype "passive"))
      (node (ref "D2") (pin "2") (pinfunction "2_2") (pintype "passive"))
      (node (ref "J1") (pin "2") (pinfunction "2_2") (pintype "passive"))
      (node (ref "J2") (pin "2") (pinfunction "2_2") (pintype "passive"))
      (node (ref "J3") (pin "2") (pinfunction "2_2") (pintype "passive"))
      (node (ref "J4") (pin "2") (pinfunction "2_2") (pintype "passive"))
      (node (ref "J5") (pin "2") (pinfunction "2_2") (pintype "passive"))
      (node (ref "J6") (pin "2") (pinfunction "2_2") (pintype "passive"))
      (node (ref "R1") (pin "2") (pinfunction "2_2") (pintype "passive"))
      (node (ref "U7") (pin "3") (pinfunction "Vin_3") (pintype "power_in"))
    )
    (net (code "5") (name "+V_Bat") (class "Default")
      (node (ref "C1") (pin "2") (pinfunction "2_2") (pintype "passive"))
      (node (ref "C3") (pin "2") (pinfunction "2_2") (pintype "passive"))
      (node (ref "Cin") (pin "2") (pinfunction "2_2") (pintype "passive"))
      (node (ref "L1") (pin "1") (pinfunction "1_1") (pintype "passive"))
      (node (ref "Li-Po") (pin "1") (pinfunction "1_1") (pintype "passive"))
      (node (ref "Pwr_But") (pin "2") (pinfunction "2_2") (pintype "passive"))
      (node (ref "U1") (pin "1") (pinfunction "Vin_1") (pintype "power_in"))
      (node (ref "U2") (pin "5") (pinfunction "Vin_5") (pintype "power_in"))
      (node (ref "U3") (pin "3") (pinfunction "BAT_3") (pintype "power_in"))
    )
    (net (code "6") (name "/ESP_I2C_SCL") (class "Default")
      (node (ref "RPI") (pin "6") (pinfunction "6_6") (pintype "passive"))
      (node (ref "U5") (pin "36") (pinfunction "IO22_36") (pintype "bidirectional"))
    )
    (net (code "7") (name "/ESP_I2C_SDA") (class "Default")
      (node (ref "RPI") (pin "4") (pinfunction "4_4") (pintype "passive"))
      (node (ref "U5") (pin "33") (pinfunction "IO21_33") (pintype "bidirectional"))
    )
    (net (code "8") (name "/ESP_RX") (class "Default")
      (node (ref "EspUART") (pin "2") (pinfunction "2_2") (pintype "passive"))
      (node (ref "RPI") (pin "7") (pinfunction "7_7") (pintype "passive"))
      (node (ref "U5") (pin "34") (pinfunction "RXD0_34") (pintype "bidirectional"))
    )
    (net (code "9") (name "/ESP_TX") (class "Default")
      (node (ref "EspUART") (pin "1") (pinfunction "1_1") (pintype "passive"))
      (node (ref "RPI") (pin "9") (pinfunction "9_9") (pintype "passive"))
      (node (ref "U5") (pin "35") (pinfunction "TXD0_35") (pintype "bidirectional"))
    )
    (net (code "10") (name "/HSPI_CS_A{slash}G") (class "Default")
      (node (ref "U5") (pin "11") (pinfunction "IO26_11") (pintype "bidirectional"))
      (node (ref "U6") (pin "7") (pinfunction "CS_A/G_7") (pintype "input"))
    )
    (net (code "11") (name "/HSPI_CS_LCD1") (class "Default")
      (node (ref "J1") (pin "40") (pinfunction "40_40") (pintype "passive"))
      (node (ref "U5") (pin "23") (pinfunction "IO15_23") (pintype "bidirectional"))
    )
    (net (code "12") (name "/HSPI_CS_LCD2") (class "Default")
      (node (ref "J2") (pin "40") (pinfunction "40_40") (pintype "passive"))
      (node (ref "U5") (pin "24") (pinfunction "IO2_24") (pintype "bidirectional"))
    )
    (net (code "13") (name "/HSPI_CS_LCD3") (class "Default")
      (node (ref "J3") (pin "40") (pinfunction "40_40") (pintype "passive"))
      (node (ref "U5") (pin "25") (pinfunction "IO0_25") (pintype "bidirectional"))
    )
    (net (code "14") (name "/HSPI_CS_M") (class "Default")
      (node (ref "U5") (pin "12") (pinfunction "IO27_12") (pintype "bidirectional"))
      (node (ref "U6") (pin "8") (pinfunction "CS_M_8") (pintype "input"))
    )
    (net (code "15") (name "/HSPI_MISO") (class "Default")
      (node (ref "U5") (pin "14") (pinfunction "IO12_14") (pintype "bidirectional"))
      (node (ref "U6") (pin "5") (pinfunction "SDO_A/G_5") (pintype "input"))
      (node (ref "U6") (pin "6") (pinfunction "SDO_M_6") (pintype "input"))
    )
    (net (code "16") (name "/HSPI_MOSI") (class "Default")
      (node (ref "J1") (pin "38") (pinfunction "38_38") (pintype "passive"))
      (node (ref "J2") (pin "38") (pinfunction "38_38") (pintype "passive"))
      (node (ref "J3") (pin "38") (pinfunction "38_38") (pintype "passive"))
      (node (ref "U5") (pin "16") (pinfunction "IO13_16") (pintype "bidirectional"))
      (node (ref "U6") (pin "4") (pinfunction "SDA/SDI/SDO_4") (pintype "input"))
    )
    (net (code "17") (name "/HSPI_SCLK") (class "Default")
      (node (ref "J1") (pin "39") (pinfunction "39_39") (pintype "passive"))
      (node (ref "J2") (pin "39") (pinfunction "39_39") (pintype "passive"))
      (node (ref "J3") (pin "39") (pinfunction "39_39") (pintype "passive"))
      (node (ref "U5") (pin "13") (pinfunction "IO14_13") (pintype "bidirectional"))
      (node (ref "U6") (pin "2") (pinfunction "SCL/SPC_2") (pintype "input"))
    )
    (net (code "18") (name "/INT_Touch") (class "Default")
      (node (ref "U4") (pin "10") (pinfunction "PA0_10") (pintype "bidirectional"))
      (node (ref "U5") (pin "8") (pinfunction "IO32_8") (pintype "bidirectional"))
    )
    (net (code "19") (name "/INT_Touch1") (class "Default")
      (node (ref "JS1") (pin "2") (pinfunction "2_2") (pintype "passive"))
      (node (ref "U4") (pin "42") (pinfunction "PB6_42") (pintype "bidirectional"))
    )
    (net (code "20") (name "/INT_Touch2") (class "Default")
      (node (ref "JS2") (pin "2") (pinfunction "2_2") (pintype "passive"))
      (node (ref "U4") (pin "43") (pinfunction "PB7_43") (pintype "bidirectional"))
    )
    (net (code "21") (name "/INT_Touch3") (class "Default")
      (node (ref "JS3") (pin "2") (pinfunction "2_2") (pintype "passive"))
      (node (ref "U4") (pin "45") (pinfunction "PB8_45") (pintype "bidirectional"))
    )
    (net (code "22") (name "/INT_Touch4") (class "Default")
      (node (ref "JS4") (pin "2") (pinfunction "2_2") (pintype "passive"))
      (node (ref "U4") (pin "46") (pinfunction "PB9_46") (pintype "bidirectional"))
    )
    (net (code "23") (name "/INT_Touch5") (class "Default")
      (node (ref "JS5") (pin "2") (pinfunction "2_2") (pintype "passive"))
      (node (ref "U4") (pin "21") (pinfunction "PB10_21") (pintype "bidirectional"))
    )
    (net (code "24") (name "/INT_Touch6") (class "Default")
      (node (ref "J6") (pin "7") (pinfunction "7_7") (pintype "passive"))
      (node (ref "U4") (pin "22") (pinfunction "PB11_22") (pintype "bidirectional"))
    )
    (net (code "25") (name "/LCD_LED_PWM1") (class "Default")
      (node (ref "R9") (pin "1") (pinfunction "1_1") (pintype "passive"))
      (node (ref "U4") (pin "18") (pinfunction "PB0_18") (pintype "bidirectional"))
    )
    (net (code "26") (name "/LCD_LED_PWM2") (class "Default")
      (node (ref "R10") (pin "1") (pinfunction "1_1") (pintype "passive"))
      (node (ref "U4") (pin "19") (pinfunction "PB1_19") (pintype "bidirectional"))
    )
    (net (code "27") (name "/LCD_LED_PWM3") (class "Default")
      (node (ref "R13") (pin "1") (pinfunction "1_1") (pintype "passive"))
      (node (ref "U4") (pin "20") (pinfunction "PB2_20") (pintype "bidirectional"))
    )
    (net (code "28") (name "/LCD_LED_PWM4") (class "Default")
      (node (ref "R14") (pin "1") (pinfunction "1_1") (pintype "passive"))
      (node (ref "U4") (pin "39") (pinfunction "PB3_39") (pintype "bidirectional"))
    )
    (net (code "29") (name "/LCD_LED_PWM5") (class "Default")
      (node (ref "R17") (pin "1") (pinfunction "1_1") (pintype "passive"))
      (node (ref "U4") (pin "40") (pinfunction "PB4_40") (pintype "bidirectional"))
    )
    (net (code "30") (name "/LCD_LED_PWM6") (class "Default")
      (node (ref "R18") (pin "1") (pinfunction "1_1") (pintype "passive"))
      (node (ref "U4") (pin "41") (pinfunction "PB5_41") (pintype "bidirectional"))
    )
    (net (code "31") (name "/Reset_LCD&Touch") (class "Default")
      (node (ref "J1") (pin "37") (pinfunction "37_37") (pintype "passive"))
      (node (ref "J2") (pin "37") (pinfunction "37_37") (pintype "passive"))
      (node (ref "J3") (pin "37") (pinfunction "37_37") (pintype "passive"))
      (node (ref "J4") (pin "37") (pinfunction "37_37") (pintype "passive"))
      (node (ref "J5") (pin "37") (pinfunction "37_37") (pintype "passive"))
      (node (ref "J6") (pin "6") (pinfunction "6_6") (pintype "passive"))
      (node (ref "JS1") (pin "1") (pinfunction "1_1") (pintype "passive"))
      (node (ref "JS2") (pin "1") (pinfunction "1_1") (pintype "passive"))
      (node (ref "JS3") (pin "1") (pinfunction "1_1") (pintype "passive"))
      (node (ref "JS4") (pin "1") (pinfunction "1_1") (pintype "passive"))
      (node (ref "JS5") (pin "1") (pinfunction "1_1") (pintype "passive"))
      (node (ref "U5") (pin "9") (pinfunction "IO33_9") (pintype "bidirectional"))
    )
    (net (code "32") (name "/SHDN") (class "Default")
      (node (ref "D7") (pin "1") (pinfunction "1_1") (pintype "passive"))
      (node (ref "R5") (pin "2") (pinfunction "2_2") (pintype "passive"))
      (node (ref "U5") (pin "10") (pinfunction "IO25_10") (pintype "bidirectional"))
    )
    (net (code "33") (name "/STM_I2C_SCL") (class "Default")
      (node (ref "J6") (pin "8") (pinfunction "8_8") (pintype "passive"))
      (node (ref "JS1") (pin "3") (pinfunction "3_3") (pintype "passive"))
      (node (ref "JS2") (pin "3") (pinfunction "3_3") (pintype "passive"))
      (node (ref "JS3") (pin "3") (pinfunction "3_3") (pintype "passive"))
      (node (ref "JS4") (pin "3") (pinfunction "3_3") (pintype "passive"))
      (node (ref "JS5") (pin "3") (pinfunction "3_3") (pintype "passive"))
      (node (ref "U4") (pin "30") (pinfunction "PA9_30") (pintype "bidirectional"))
    )
    (net (code "34") (name "/STM_I2C_SDA") (class "Default")
      (node (ref "J6") (pin "9") (pinfunction "9_9") (pintype "passive"))
      (node (ref "JS1") (pin "4") (pinfunction "4_4") (pintype "passive"))
      (node (ref "JS2") (pin "4") (pinfunction "4_4") (pintype "passive"))
      (node (ref "JS3") (pin "4") (pinfunction "4_4") (pintype "passive"))
      (node (ref "JS4") (pin "4") (pinfunction "4_4") (pintype "passive"))
      (node (ref "JS5") (pin "4") (pinfunction "4_4") (pintype "passive"))
      (node (ref "U4") (pin "31") (pinfunction "PA10_31") (pintype "bidirectional"))
    )
    (net (code "35") (name "/SWCLK") (class "Default")
      (node (ref "SWD") (pin "2") (pinfunction "2_2") (pintype "passive"))
      (node (ref "U4") (pin "37") (pinfunction "PA14(SWCLK)_37") (pintype "bidirectional"))
    )
    (net (code "36") (name "/SWDIO") (class "Default")
      (node (ref "SWD") (pin "4") (pinfunction "4_4") (pintype "passive"))
      (node (ref "U4") (pin "34") (pinfunction "PA13(SWDIO)_34") (pintype "bidirectional"))
    )
    (net (code "37") (name "/VSPI_CS_LCD4") (class "Default")
      (node (ref "J4") (pin "40") (pinfunction "40_40") (pintype "passive"))
      (node (ref "U5") (pin "26") (pinfunction "IO4_26") (pintype "bidirectional"))
    )
    (net (code "38") (name "/VSPI_CS_LCD5") (class "Default")
      (node (ref "J5") (pin "40") (pinfunction "40_40") (pintype "passive"))
      (node (ref "U5") (pin "27") (pinfunction "IO16_27") (pintype "bidirectional"))
    )
    (net (code "39") (name "/VSPI_CS_LCD6") (class "Default")
      (node (ref "J6") (pin "12") (pinfunction "12_12") (pintype "passive"))
      (node (ref "U5") (pin "28") (pinfunction "IO17_28") (pintype "bidirectional"))
    )
    (net (code "40") (name "/VSPI_CS_STM") (class "Default")
      (node (ref "U4") (pin "14") (pinfunction "PA4_14") (pintype "bidirectional"))
      (node (ref "U5") (pin "29") (pinfunction "IO5_29") (pintype "bidirectional"))
    )
    (net (code "41") (name "/VSPI_MISO") (class "Default")
      (node (ref "U4") (pin "16") (pinfunction "PA6_16") (pintype "bidirectional"))
      (node (ref "U5") (pin "31") (pinfunction "IO19_31") (pintype "bidirectional"))
    )
    (net (code "42") (name "/VSPI_MOSI") (class "Default")
      (node (ref "J4") (pin "38") (pinfunction "38_38") (pintype "passive"))
      (node (ref "J5") (pin "38") (pinfunction "38_38") (pintype "passive"))
      (node (ref "J6") (pin "10") (pinfunction "10_10") (pintype "passive"))
      (node (ref "U4") (pin "17") (pinfunction "PA7_17") (pintype "bidirectional"))
      (node (ref "U5") (pin "37") (pinfunction "IO23_37") (pintype "bidirectional"))
    )
    (net (code "43") (name "/VSPI_SCLK") (class "Default")
      (node (ref "J4") (pin "39") (pinfunction "39_39") (pintype "passive"))
      (node (ref "J5") (pin "39") (pinfunction "39_39") (pintype "passive"))
      (node (ref "J6") (pin "11") (pinfunction "11_11") (pintype "passive"))
      (node (ref "U4") (pin "15") (pinfunction "PA5_15") (pintype "bidirectional"))
      (node (ref "U5") (pin "30") (pinfunction "IO18_30") (pintype "bidirectional"))
    )
    (net (code "44") (name "GND") (class "Default")
      (node (ref "B1") (pin "2") (pinfunction "2_2") (pintype "passive"))
      (node (ref "C1") (pin "1") (pinfunction "1_1") (pintype "passive"))
      (node (ref "C10") (pin "2") (pinfunction "2_2") (pintype "passive"))
      (node (ref "C11") (pin "2") (pinfunction "2_2") (pintype "passive"))
      (node (ref "C12") (pin "2") (pinfunction "2_2") (pintype "passive"))
      (node (ref "C13") (pin "2") (pinfunction "2_2") (pintype "passive"))
      (node (ref "C14") (pin "2") (pinfunction "2_2") (pintype "passive"))
      (node (ref "C15") (pin "2") (pinfunction "2_2") (pintype "passive"))
      (node (ref "C16") (pin "2") (pinfunction "2_2") (pintype "passive"))
      (node (ref "C17") (pin "2") (pinfunction "2_2") (pintype "passive"))
      (node (ref "C18") (pin "2") (pinfunction "2_2") (pintype "passive"))
      (node (ref "C19") (pin "2") (pinfunction "2_2") (pintype "passive"))
      (node (ref "C2") (pin "1") (pinfunction "1_1") (pintype "passive"))
      (node (ref "C20") (pin "1") (pinfunction "1_1") (pintype "passive"))
      (node (ref "C21") (pin "1") (pinfunction "1_1") (pintype "passive"))
      (node (ref "C22") (pin "1") (pinfunction "1_1") (pintype "passive"))
      (node (ref "C23") (pin "1") (pinfunction "1_1") (pintype "passive"))
      (node (ref "C24") (pin "1") (pinfunction "1_1") (pintype "passive"))
      (node (ref "C25") (pin "2") (pinfunction "2_2") (pintype "passive"))
      (node (ref "C3") (pin "1") (pinfunction "1_1") (pintype "passive"))
      (node (ref "C4") (pin "1") (pinfunction "1_1") (pintype "passive"))
      (node (ref "C5") (pin "1") (pinfunction "1_1") (pintype "passive"))
      (node (ref "C6") (pin "1") (pinfunction "1_1") (pintype "passive"))
      (node (ref "C7") (pin "1") (pinfunction "1_1") (pintype "passive"))
      (node (ref "C8") (pin "2") (pinfunction "2_2") (pintype "passive"))
      (node (ref "C9") (pin "2") (pinfunction "2_2") (pintype "passive"))
      (node (ref "Charge Inductors") (pin "7") (pinfunction "7_7") (pintype "passive"))
      (node (ref "Cin") (pin "1") (pinfunction "1_1") (pintype "passive"))
      (node (ref "D4") (pin "1") (pinfunction "1_1") (pintype "passive"))
      (node (ref "EspUART") (pin "3") (pinfunction "3_3") (pintype "passive"))
      (node (ref "J1") (pin "29") (pinfunction "29_29") (pintype "passive"))
      (node (ref "J1") (pin "3") (pinfunction "3_3") (pintype "passive"))
      (node (ref "J1") (pin "32") (pinfunction "32_32") (pintype "passive"))
      (node (ref "J1") (pin "33") (pinfunction "33_33") (pintype "passive"))
      (node (ref "J1") (pin "36") (pinfunction "36_36") (pintype "passive"))
      (node (ref "J1") (pin "A") (pinfunction "Shield_A") (pintype "passive"))
      (node (ref "J2") (pin "29") (pinfunction "29_29") (pintype "passive"))
      (node (ref "J2") (pin "3") (pinfunction "3_3") (pintype "passive"))
      (node (ref "J2") (pin "32") (pinfunction "32_32") (pintype "passive"))
      (node (ref "J2") (pin "33") (pinfunction "33_33") (pintype "passive"))
      (node (ref "J2") (pin "36") (pinfunction "36_36") (pintype "passive"))
      (node (ref "J2") (pin "A") (pinfunction "Shield_A") (pintype "passive"))
      (node (ref "J3") (pin "29") (pinfunction "29_29") (pintype "passive"))
      (node (ref "J3") (pin "3") (pinfunction "3_3") (pintype "passive"))
      (node (ref "J3") (pin "32") (pinfunction "32_32") (pintype "passive"))
      (node (ref "J3") (pin "33") (pinfunction "33_33") (pintype "passive"))
      (node (ref "J3") (pin "36") (pinfunction "36_36") (pintype "passive"))
      (node (ref "J3") (pin "A") (pinfunction "Shield_A") (pintype "passive"))
      (node (ref "J4") (pin "29") (pinfunction "29_29") (pintype "passive"))
      (node (ref "J4") (pin "3") (pinfunction "3_3") (pintype "passive"))
      (node (ref "J4") (pin "32") (pinfunction "32_32") (pintype "passive"))
      (node (ref "J4") (pin "33") (pinfunction "33_33") (pintype "passive"))
      (node (ref "J4") (pin "36") (pinfunction "36_36") (pintype "passive"))
      (node (ref "J4") (pin "A") (pinfunction "Shield_A") (pintype "passive"))
      (node (ref "J5") (pin "29") (pinfunction "29_29") (pintype "passive"))
      (node (ref "J5") (pin "3") (pinfunction "3_3") (pintype "passive"))
      (node (ref "J5") (pin "32") (pinfunction "32_32") (pintype "passive"))
      (node (ref "J5") (pin "33") (pinfunction "33_33") (pintype "passive"))
      (node (ref "J5") (pin "36") (pinfunction "36_36") (pintype "passive"))
      (node (ref "J5") (pin "A") (pinfunction "Shield_A") (pintype "passive"))
      (node (ref "J6") (pin "3") (pinfunction "3_3") (pintype "passive"))
      (node (ref "J6") (pin "A") (pinfunction "Shield_A") (pintype "passive"))
      (node (ref "JS1") (pin "6") (pinfunction "6_6") (pintype "passive"))
      (node (ref "JS1") (pin "A") (pinfunction "Shield_A") (pintype "passive"))
      (node (ref "JS2") (pin "6") (pinfunction "6_6") (pintype "passive"))
      (node (ref "JS2") (pin "A") (pinfunction "Shield_A") (pintype "passive"))
      (node (ref "JS3") (pin "6") (pinfunction "6_6") (pintype "passive"))
      (node (ref "JS3") (pin "A") (pinfunction "Shield_A") (pintype "passive"))
      (node (ref "JS4") (pin "6") (pinfunction "6_6") (pintype "passive"))
      (node (ref "JS4") (pin "A") (pinfunction "Shield_A") (pintype "passive"))
      (node (ref "JS5") (pin "6") (pinfunction "6_6") (pintype "passive"))
      (node (ref "JS5") (pin "A") (pinfunction "Shield_A") (pintype "passive"))
      (node (ref "Li-Po") (pin "2") (pinfunction "2_2") (pintype "passive"))
      (node (ref "R11") (pin "1") (pinfunction "1_1") (pintype "passive"))
      (node (ref "R12") (pin "1") (pinfunction "1_1") (pintype "passive"))
      (node (ref "R15") (pin "1") (pinfunction "1_1") (pintype "passive"))
      (node (ref "R16") (pin "1") (pinfunction "1_1") (pintype "passive"))
      (node (ref "R19") (pin "1") (pinfunction "1_1") (pintype "passive"))
      (node (ref "R2") (pin "2") (pinfunction "2_2") (pintype "passive"))
      (node (ref "R20") (pin "1") (pinfunction "1_1") (pintype "passive"))
      (node (ref "R21") (pin "2") (pinfunction "2_2") (pintype "passive"))
      (node (ref "R3") (pin "2") (pinfunction "2_2") (pintype "passive"))
      (node (ref "R7") (pin "1") (pinfunction "1_1") (pintype "passive"))
      (node (ref "R8") (pin "1") (pinfunction "1_1") (pintype "passive"))
      (node (ref "RPI") (pin "10") (pinfunction "10_10") (pintype "passive"))
      (node (ref "RPI") (pin "13") (pinfunction "13_13") (pintype "passive"))
      (node (ref "RPI") (pin "19") (pinfunction "19_19") (pintype "passive"))
      (node (ref "RPI") (pin "26") (pinfunction "26_26") (pintype "passive"))
      (node (ref "RPI") (pin "29") (pinfunction "29_29") (pintype "passive"))
      (node (ref "RPI") (pin "33") (pinfunction "33_33") (pintype "passive"))
      (node (ref "RPI") (pin "40") (pinfunction "40_40") (pintype "passive"))
      (node (ref "RPI") (pin "5") (pinfunction "5_5") (pintype "passive"))
      (node (ref "SWD") (pin "3") (pinfunction "3_3") (pintype "passive"))
      (node (ref "U1") (pin "2") (pinfunction "GND_2") (pintype "power_in"))
      (node (ref "U2") (pin "2") (pinfunction "GND_2") (pintype "power_in"))
      (node (ref "U3") (pin "2") (pinfunction "GND_2") (pintype "power_in"))
      (node (ref "U4") (pin "23") (pinfunction "VSS_23") (pintype "power_in"))
      (node (ref "U4") (pin "35") (pinfunction "VSS_35") (pintype "power_in"))
      (node (ref "U4") (pin "47") (pinfunction "VSS_47") (pintype "power_in"))
      (node (ref "U4") (pin "8") (pinfunction "VSSA_8") (pintype "power_in"))
      (node (ref "U5") (pin "1") (pinfunction "GND_1") (pintype "power_in"))
      (node (ref "U5") (pin "15") (pinfunction "GND_15") (pintype "power_in"))
      (node (ref "U5") (pin "38") (pinfunction "GND_38") (pintype "power_in"))
      (node (ref "U5") (pin "39") (pinfunction "GND_39") (pintype "power_in"))
      (node (ref "U6") (pin "14") (pinfunction "GND_14") (pintype "power_in"))
      (node (ref "U6") (pin "15") (pinfunction "GND_15") (pintype "power_in"))
      (node (ref "U6") (pin "16") (pinfunction "GND_16") (pintype "power_in"))
      (node (ref "U6") (pin "17") (pinfunction "GND_17") (pintype "power_in"))
      (node (ref "U6") (pin "18") (pinfunction "GND_18") (pintype "power_in"))
      (node (ref "U6") (pin "19") (pinfunction "GND_19") (pintype "power_in"))
      (node (ref "U6") (pin "20") (pinfunction "GND_20") (pintype "power_in"))
      (node (ref "U7") (pin "1") (pinfunction "GND_1") (pintype "power_in"))
      (node (ref "Y1") (pin "GND") (pinfunction "GND_GND") (pintype "passive"))
    )
    (net (code "45") (name "Net-(Charge Inductors-Pad1)") (class "Default")
      (node (ref "Charge Inductors") (pin "1") (pinfunction "1_1") (pintype "passive"))
      (node (ref "D1") (pin "1") (pinfunction "1_1") (pintype "passive"))
    )
    (net (code "46") (name "Net-(Charge Inductors-Pad2)") (class "Default")
      (node (ref "Charge Inductors") (pin "2") (pinfunction "2_2") (pintype "passive"))
      (node (ref "D3") (pin "1") (pinfunction "1_1") (pintype "passive"))
    )
    (net (code "47") (name "Net-(Charge Inductors-Pad3)") (class "Default")
      (node (ref "Charge Inductors") (pin "3") (pinfunction "3_3") (pintype "passive"))
      (node (ref "D5") (pin "1") (pinfunction "1_1") (pintype "passive"))
    )
    (net (code "48") (name "Net-(Charge Inductors-Pad4)") (class "Default")
      (node (ref "Charge Inductors") (pin "4") (pinfunction "4_4") (pintype "passive"))
      (node (ref "D6") (pin "1") (pinfunction "1_1") (pintype "passive"))
    )
    (net (code "49") (name "Net-(Charge Inductors-Pad5)") (class "Default")
      (node (ref "Charge Inductors") (pin "5") (pinfunction "5_5") (pintype "passive"))
      (node (ref "D9") (pin "1") (pinfunction "1_1") (pintype "passive"))
    )
    (net (code "50") (name "Net-(Charge Inductors-Pad6)") (class "Default")
      (node (ref "Charge Inductors") (pin "6") (pinfunction "6_6") (pintype "passive"))
      (node (ref "D10") (pin "1") (pinfunction "1_1") (pintype "passive"))
    )
    (net (code "51") (name "Net-(D7-Pad2)") (class "Default")
      (node (ref "D7") (pin "2") (pinfunction "2_2") (pintype "passive"))
      (node (ref "Pwr_But") (pin "1") (pinfunction "1_1") (pintype "passive"))
      (node (ref "R4") (pin "1") (pinfunction "1_1") (pintype "passive"))
    )
    (net (code "52") (name "Net-(D8-Pad2)") (class "Default")
      (node (ref "D8") (pin "2") (pinfunction "2_2") (pintype "passive"))
      (node (ref "R6") (pin "2") (pinfunction "2_2") (pintype "passive"))
    )
    (net (code "53") (name "Net-(J1-Pad1)") (class "Default")
      (node (ref "J1") (pin "1") (pinfunction "1_1") (pintype "passive"))
      (node (ref "Q1") (pin "3") (pinfunction "3_3") (pintype "passive"))
    )
    (net (code "54") (name "Net-(J2-Pad1)") (class "Default")
      (node (ref "J2") (pin "1") (pinfunction "1_1") (pintype "passive"))
      (node (ref "Q2") (pin "3") (pinfunction "3_3") (pintype "passive"))
    )
    (net (code "55") (name "Net-(J3-Pad1)") (class "Default")
      (node (ref "J3") (pin "1") (pinfunction "1_1") (pintype "passive"))
      (node (ref "Q3") (pin "3") (pinfunction "3_3") (pintype "passive"))
    )
    (net (code "56") (name "Net-(J4-Pad1)") (class "Default")
      (node (ref "J4") (pin "1") (pinfunction "1_1") (pintype "passive"))
      (node (ref "Q4") (pin "3") (pinfunction "3_3") (pintype "passive"))
    )
    (net (code "57") (name "Net-(J5-Pad1)") (class "Default")
      (node (ref "J5") (pin "1") (pinfunction "1_1") (pintype "passive"))
      (node (ref "Q5") (pin "3") (pinfunction "3_3") (pintype "passive"))
    )
    (net (code "58") (name "Net-(J6-Pad1)") (class "Default")
      (node (ref "J6") (pin "1") (pinfunction "1_1") (pintype "passive"))
      (node (ref "Q6") (pin "3") (pinfunction "3_3") (pintype "passive"))
    )
    (net (code "59") (name "Net-(Q1-Pad1)") (class "Default")
      (node (ref "Q1") (pin "1") (pinfunction "1_1") (pintype "passive"))
      (node (ref "R9") (pin "2") (pinfunction "2_2") (pintype "passive"))
    )
    (net (code "60") (name "Net-(Q1-Pad2)") (class "Default")
      (node (ref "Q1") (pin "2") (pinfunction "2_2") (pintype "passive"))
      (node (ref "R11") (pin "2") (pinfunction "2_2") (pintype "passive"))
    )
    (net (code "61") (name "Net-(Q2-Pad1)") (class "Default")
      (node (ref "Q2") (pin "1") (pinfunction "1_1") (pintype "passive"))
      (node (ref "R10") (pin "2") (pinfunction "2_2") (pintype "passive"))
    )
    (net (code "62") (name "Net-(Q2-Pad2)") (class "Default")
      (node (ref "Q2") (pin "2") (pinfunction "2_2") (pintype "passive"))
      (node (ref "R12") (pin "2") (pinfunction "2_2") (pintype "passive"))
    )
    (net (code "63") (name "Net-(Q3-Pad1)") (class "Default")
      (node (ref "Q3") (pin "1") (pinfunction "1_1") (pintype "passive"))
      (node (ref "R13") (pin "2") (pinfunction "2_2") (pintype "passive"))
    )
    (net (code "64") (name "Net-(Q3-Pad2)") (class "Default")
      (node (ref "Q3") (pin "2") (pinfunction "2_2") (pintype "passive"))
      (node (ref "R15") (pin "2") (pinfunction "2_2") (pintype "passive"))
    )
    (net (code "65") (name "Net-(Q4-Pad1)") (class "Default")
      (node (ref "Q4") (pin "1") (pinfunction "1_1") (pintype "passive"))
      (node (ref "R14") (pin "2") (pinfunction "2_2") (pintype "passive"))
    )
    (net (code "66") (name "Net-(Q4-Pad2)") (class "Default")
      (node (ref "Q4") (pin "2") (pinfunction "2_2") (pintype "passive"))
      (node (ref "R16") (pin "2") (pinfunction "2_2") (pintype "passive"))
    )
    (net (code "67") (name "Net-(Q5-Pad1)") (class "Default")
      (node (ref "Q5") (pin "1") (pinfunction "1_1") (pintype "passive"))
      (node (ref "R17") (pin "2") (pinfunction "2_2") (pintype "passive"))
    )
    (net (code "68") (name "Net-(Q5-Pad2)") (class "Default")
      (node (ref "Q5") (pin "2") (pinfunction "2_2") (pintype "passive"))
      (node (ref "R19") (pin "2") (pinfunction "2_2") (pintype "passive"))
    )
    (net (code "69") (name "Net-(Q6-Pad1)") (class "Default")
      (node (ref "Q6") (pin "1") (pinfunction "1_1") (pintype "passive"))
      (node (ref "R18") (pin "2") (pinfunction "2_2") (pintype "passive"))
    )
    (net (code "70") (name "Net-(Q6-Pad2)") (class "Default")
      (node (ref "Q6") (pin "2") (pinfunction "2_2") (pintype "passive"))
      (node (ref "R20") (pin "2") (pinfunction "2_2") (pintype "passive"))
    )
    (net (code "71") (name "Net-(U1-EN)") (class "Default")
      (node (ref "R3") (pin "1") (pinfunction "1_1") (pintype "passive"))
      (node (ref "R4") (pin "2") (pinfunction "2_2") (pintype "passive"))
      (node (ref "U1") (pin "3") (pinfunction "EN_3") (pintype "power_in"))
    )
    (net (code "72") (name "Net-(U2-FB)") (class "Default")
      (node (ref "Cf") (pin "1") (pinfunction "1_1") (pintype "passive"))
      (node (ref "R1") (pin "1") (pinfunction "1_1") (pintype "passive"))
      (node (ref "R2") (pin "1") (pinfunction "1_1") (pintype "passive"))
      (node (ref "U2") (pin "3") (pinfunction "FB_3") (pintype "passive"))
    )
    (net (code "73") (name "Net-(U2-SHDN)") (class "Default")
      (node (ref "R5") (pin "1") (pinfunction "1_1") (pintype "passive"))
      (node (ref "R7") (pin "2") (pinfunction "2_2") (pintype "passive"))
      (node (ref "U2") (pin "4") (pinfunction "SHDN_4") (pintype "power_in"))
    )
    (net (code "74") (name "Net-(U2-SW)") (class "Default")
      (node (ref "D2") (pin "1") (pinfunction "1_1") (pintype "passive"))
      (node (ref "L1") (pin "2") (pinfunction "2_2") (pintype "passive"))
      (node (ref "U2") (pin "1") (pinfunction "SW_1") (pintype "passive"))
    )
    (net (code "75") (name "Net-(U3-CHRG)") (class "Default")
      (node (ref "R6") (pin "1") (pinfunction "1_1") (pintype "passive"))
      (node (ref "U3") (pin "1") (pinfunction "CHRG_1") (pintype "passive"))
    )
    (net (code "76") (name "Net-(U3-PROG)") (class "Default")
      (node (ref "R8") (pin "2") (pinfunction "2_2") (pintype "passive"))
      (node (ref "U3") (pin "5") (pinfunction "PROG_5") (pintype "passive"))
    )
    (net (code "77") (name "Net-(U4-BOOT0)") (class "Default")
      (node (ref "R21") (pin "1") (pinfunction "1_1") (pintype "passive"))
      (node (ref "U4") (pin "44") (pinfunction "BOOT0_44") (pintype "input"))
    )
    (net (code "78") (name "Net-(U4-PF0-OSC_IN(PF0))") (class "Default")
      (node (ref "C13") (pin "1") (pinfunction "1_1") (pintype "passive"))
      (node (ref "U4") (pin "5") (pinfunction "PF0-OSC_IN(PF0)_5") (pintype "bidirectional"))
      (node (ref "Y1") (pin "1") (pinfunction "1_1") (pintype "passive"))
    )
    (net (code "79") (name "Net-(U4-PF1-OSC_OUT(PF1))") (class "Default")
      (node (ref "C15") (pin "1") (pinfunction "1_1") (pintype "passive"))
      (node (ref "U4") (pin "6") (pinfunction "PF1-OSC_OUT(PF1)_6") (pintype "bidirectional"))
      (node (ref "Y1") (pin "2") (pinfunction "2_2") (pintype "passive"))
    )
    (net (code "80") (name "Net-(U5-EN)") (class "Default")
      (node (ref "B1") (pin "1") (pinfunction "1_1") (pintype "passive"))
      (node (ref "C25") (pin "1") (pinfunction "1_1") (pintype "passive"))
      (node (ref "R22") (pin "1") (pinfunction "1_1") (pintype "passive"))
      (node (ref "U5") (pin "3") (pinfunction "EN_3") (pintype "input"))
    )
    (net (code "81") (name "Net-(U6-C1)") (class "Default")
      (node (ref "C12") (pin "1") (pinfunction "1_1") (pintype "passive"))
      (node (ref "U6") (pin "24") (pinfunction "C1_24") (pintype "open_collector"))
    )
    (net (code "82") (name "Net-(U6-CAP)") (class "Default")
      (node (ref "C11") (pin "1") (pinfunction "1_1") (pintype "passive"))
      (node (ref "U6") (pin "21") (pinfunction "CAP_21") (pintype "open_collector"))
    )
    (net (code "83") (name "unconnected-(J1-Pad5)") (class "Default")
      (node (ref "J1") (pin "5") (pinfunction "5_5") (pintype "passive"))
    )
    (net (code "84") (name "unconnected-(J1-Pad6)") (class "Default")
      (node (ref "J1") (pin "6") (pinfunction "6_6") (pintype "passive"))
    )
    (net (code "85") (name "unconnected-(J1-Pad7)") (class "Default")
      (node (ref "J1") (pin "7") (pinfunction "7_7") (pintype "passive"))
    )
    (net (code "86") (name "unconnected-(J1-Pad8)") (class "Default")
      (node (ref "J1") (pin "8") (pinfunction "8_8") (pintype "passive"))
    )
    (net (code "87") (name "unconnected-(J1-Pad9)") (class "Default")
      (node (ref "J1") (pin "9") (pinfunction "9_9") (pintype "passive"))
    )
    (net (code "88") (name "unconnected-(J1-Pad10)") (class "Default")
      (node (ref "J1") (pin "10") (pinfunction "10_10") (pintype "passive"))
    )
    (net (code "89") (name "unconnected-(J1-Pad11)") (class "Default")
      (node (ref "J1") (pin "11") (pinfunction "11_11") (pintype "passive"))
    )
    (net (code "90") (name "unconnected-(J1-Pad12)") (class "Default")
      (node (ref "J1") (pin "12") (pinfunction "12_12") (pintype "passive"))
    )
    (net (code "91") (name "unconnected-(J1-Pad13)") (class "Default")
      (node (ref "J1") (pin "13") (pinfunction "13_13") (pintype "passive"))
    )
    (net (code "92") (name "unconnected-(J1-Pad14)") (class "Default")
      (node (ref "J1") (pin "14") (pinfunction "14_14") (pintype "passive"))
    )
    (net (code "93") (name "unconnected-(J1-Pad15)") (class "Default")
      (node (ref "J1") (pin "15") (pinfunction "15_15") (pintype "passive"))
    )
    (net (code "94") (name "unconnected-(J1-Pad16)") (class "Default")
      (node (ref "J1") (pin "16") (pinfunction "16_16") (pintype "passive"))
    )
    (net (code "95") (name "unconnected-(J1-Pad17)") (class "Default")
      (node (ref "J1") (pin "17") (pinfunction "17_17") (pintype "passive"))
    )
    (net (code "96") (name "unconnected-(J1-Pad18)") (class "Default")
      (node (ref "J1") (pin "18") (pinfunction "18_18") (pintype "passive"))
    )
    (net (code "97") (name "unconnected-(J1-Pad19)") (class "Default")
      (node (ref "J1") (pin "19") (pinfunction "19_19") (pintype "passive"))
    )
    (net (code "98") (name "unconnected-(J1-Pad20)") (class "Default")
      (node (ref "J1") (pin "20") (pinfunction "20_20") (pintype "passive"))
    )
    (net (code "99") (name "unconnected-(J1-Pad21)") (class "Default")
      (node (ref "J1") (pin "21") (pinfunction "21_21") (pintype "passive"))
    )
    (net (code "100") (name "unconnected-(J1-Pad22)") (class "Default")
      (node (ref "J1") (pin "22") (pinfunction "22_22") (pintype "passive"))
    )
    (net (code "101") (name "unconnected-(J1-Pad23)") (class "Default")
      (node (ref "J1") (pin "23") (pinfunction "23_23") (pintype "passive"))
    )
    (net (code "102") (name "unconnected-(J1-Pad24)") (class "Default")
      (node (ref "J1") (pin "24") (pinfunction "24_24") (pintype "passive"))
    )
    (net (code "103") (name "unconnected-(J1-Pad25)") (class "Default")
      (node (ref "J1") (pin "25") (pinfunction "25_25") (pintype "passive"))
    )
    (net (code "104") (name "unconnected-(J1-Pad26)") (class "Default")
      (node (ref "J1") (pin "26") (pinfunction "26_26") (pintype "passive"))
    )
    (net (code "105") (name "unconnected-(J1-Pad27)") (class "Default")
      (node (ref "J1") (pin "27") (pinfunction "27_27") (pintype "passive"))
    )
    (net (code "106") (name "unconnected-(J1-Pad28)") (class "Default")
      (node (ref "J1") (pin "28") (pinfunction "28_28") (pintype "passive"))
    )
    (net (code "107") (name "unconnected-(J1-Pad30)") (class "Default")
      (node (ref "J1") (pin "30") (pinfunction "30_30") (pintype "passive"))
    )
    (net (code "108") (name "unconnected-(J1-Pad31)") (class "Default")
      (node (ref "J1") (pin "31") (pinfunction "31_31") (pintype "passive"))
    )
    (net (code "109") (name "unconnected-(J1-Pad34)") (class "Default")
      (node (ref "J1") (pin "34") (pinfunction "34_34") (pintype "passive"))
    )
    (net (code "110") (name "unconnected-(J1-Pad35)") (class "Default")
      (node (ref "J1") (pin "35") (pinfunction "35_35") (pintype "passive"))
    )
    (net (code "111") (name "unconnected-(J2-Pad5)") (class "Default")
      (node (ref "J2") (pin "5") (pinfunction "5_5") (pintype "passive"))
    )
    (net (code "112") (name "unconnected-(J2-Pad6)") (class "Default")
      (node (ref "J2") (pin "6") (pinfunction "6_6") (pintype "passive"))
    )
    (net (code "113") (name "unconnected-(J2-Pad7)") (class "Default")
      (node (ref "J2") (pin "7") (pinfunction "7_7") (pintype "passive"))
    )
    (net (code "114") (name "unconnected-(J2-Pad8)") (class "Default")
      (node (ref "J2") (pin "8") (pinfunction "8_8") (pintype "passive"))
    )
    (net (code "115") (name "unconnected-(J2-Pad9)") (class "Default")
      (node (ref "J2") (pin "9") (pinfunction "9_9") (pintype "passive"))
    )
    (net (code "116") (name "unconnected-(J2-Pad10)") (class "Default")
      (node (ref "J2") (pin "10") (pinfunction "10_10") (pintype "passive"))
    )
    (net (code "117") (name "unconnected-(J2-Pad11)") (class "Default")
      (node (ref "J2") (pin "11") (pinfunction "11_11") (pintype "passive"))
    )
    (net (code "118") (name "unconnected-(J2-Pad12)") (class "Default")
      (node (ref "J2") (pin "12") (pinfunction "12_12") (pintype "passive"))
    )
    (net (code "119") (name "unconnected-(J2-Pad13)") (class "Default")
      (node (ref "J2") (pin "13") (pinfunction "13_13") (pintype "passive"))
    )
    (net (code "120") (name "unconnected-(J2-Pad14)") (class "Default")
      (node (ref "J2") (pin "14") (pinfunction "14_14") (pintype "passive"))
    )
    (net (code "121") (name "unconnected-(J2-Pad15)") (class "Default")
      (node (ref "J2") (pin "15") (pinfunction "15_15") (pintype "passive"))
    )
    (net (code "122") (name "unconnected-(J2-Pad16)") (class "Default")
      (node (ref "J2") (pin "16") (pinfunction "16_16") (pintype "passive"))
    )
    (net (code "123") (name "unconnected-(J2-Pad17)") (class "Default")
      (node (ref "J2") (pin "17") (pinfunction "17_17") (pintype "passive"))
    )
    (net (code "124") (name "unconnected-(J2-Pad18)") (class "Default")
      (node (ref "J2") (pin "18") (pinfunction "18_18") (pintype "passive"))
    )
    (net (code "125") (name "unconnected-(J2-Pad19)") (class "Default")
      (node (ref "J2") (pin "19") (pinfunction "19_19") (pintype "passive"))
    )
    (net (code "126") (name "unconnected-(J2-Pad20)") (class "Default")
      (node (ref "J2") (pin "20") (pinfunction "20_20") (pintype "passive"))
    )
    (net (code "127") (name "unconnected-(J2-Pad21)") (class "Default")
      (node (ref "J2") (pin "21") (pinfunction "21_21") (pintype "passive"))
    )
    (net (code "128") (name "unconnected-(J2-Pad22)") (class "Default")
      (node (ref "J2") (pin "22") (pinfunction "22_22") (pintype "passive"))
    )
    (net (code "129") (name "unconnected-(J2-Pad23)") (class "Default")
      (node (ref "J2") (pin "23") (pinfunction "23_23") (pintype "passive"))
    )
    (net (code "130") (name "unconnected-(J2-Pad24)") (class "Default")
      (node (ref "J2") (pin "24") (pinfunction "24_24") (pintype "passive"))
    )
    (net (code "131") (name "unconnected-(J2-Pad25)") (class "Default")
      (node (ref "J2") (pin "25") (pinfunction "25_25") (pintype "passive"))
    )
    (net (code "132") (name "unconnected-(J2-Pad26)") (class "Default")
      (node (ref "J2") (pin "26") (pinfunction "26_26") (pintype "passive"))
    )
    (net (code "133") (name "unconnected-(J2-Pad27)") (class "Default")
      (node (ref "J2") (pin "27") (pinfunction "27_27") (pintype "passive"))
    )
    (net (code "134") (name "unconnected-(J2-Pad28)") (class "Default")
      (node (ref "J2") (pin "28") (pinfunction "28_28") (pintype "passive"))
    )
    (net (code "135") (name "unconnected-(J2-Pad30)") (class "Default")
      (node (ref "J2") (pin "30") (pinfunction "30_30") (pintype "passive"))
    )
    (net (code "136") (name "unconnected-(J2-Pad31)") (class "Default")
      (node (ref "J2") (pin "31") (pinfunction "31_31") (pintype "passive"))
    )
    (net (code "137") (name "unconnected-(J2-Pad34)") (class "Default")
      (node (ref "J2") (pin "34") (pinfunction "34_34") (pintype "passive"))
    )
    (net (code "138") (name "unconnected-(J2-Pad35)") (class "Default")
      (node (ref "J2") (pin "35") (pinfunction "35_35") (pintype "passive"))
    )
    (net (code "139") (name "unconnected-(J3-Pad5)") (class "Default")
      (node (ref "J3") (pin "5") (pinfunction "5_5") (pintype "passive"))
    )
    (net (code "140") (name "unconnected-(J3-Pad6)") (class "Default")
      (node (ref "J3") (pin "6") (pinfunction "6_6") (pintype "passive"))
    )
    (net (code "141") (name "unconnected-(J3-Pad7)") (class "Default")
      (node (ref "J3") (pin "7") (pinfunction "7_7") (pintype "passive"))
    )
    (net (code "142") (name "unconnected-(J3-Pad8)") (class "Default")
      (node (ref "J3") (pin "8") (pinfunction "8_8") (pintype "passive"))
    )
    (net (code "143") (name "unconnected-(J3-Pad9)") (class "Default")
      (node (ref "J3") (pin "9") (pinfunction "9_9") (pintype "passive"))
    )
    (net (code "144") (name "unconnected-(J3-Pad10)") (class "Default")
      (node (ref "J3") (pin "10") (pinfunction "10_10") (pintype "passive"))
    )
    (net (code "145") (name "unconnected-(J3-Pad11)") (class "Default")
      (node (ref "J3") (pin "11") (pinfunction "11_11") (pintype "passive"))
    )
    (net (code "146") (name "unconnected-(J3-Pad12)") (class "Default")
      (node (ref "J3") (pin "12") (pinfunction "12_12") (pintype "passive"))
    )
    (net (code "147") (name "unconnected-(J3-Pad13)") (class "Default")
      (node (ref "J3") (pin "13") (pinfunction "13_13") (pintype "passive"))
    )
    (net (code "148") (name "unconnected-(J3-Pad14)") (class "Default")
      (node (ref "J3") (pin "14") (pinfunction "14_14") (pintype "passive"))
    )
    (net (code "149") (name "unconnected-(J3-Pad15)") (class "Default")
      (node (ref "J3") (pin "15") (pinfunction "15_15") (pintype "passive"))
    )
    (net (code "150") (name "unconnected-(J3-Pad16)") (class "Default")
      (node (ref "J3") (pin "16") (pinfunction "16_16") (pintype "passive"))
    )
    (net (code "151") (name "unconnected-(J3-Pad17)") (class "Default")
      (node (ref "J3") (pin "17") (pinfunction "17_17") (pintype "passive"))
    )
    (net (code "152") (name "unconnected-(J3-Pad18)") (class "Default")
      (node (ref "J3") (pin "18") (pinfunction "18_18") (pintype "passive"))
    )
    (net (code "153") (name "unconnected-(J3-Pad19)") (class "Default")
      (node (ref "J3") (pin "19") (pinfunction "19_19") (pintype "passive"))
    )
    (net (code "154") (name "unconnected-(J3-Pad20)") (class "Default")
      (node (ref "J3") (pin "20") (pinfunction "20_20") (pintype "passive"))
    )
    (net (code "155") (name "unconnected-(J3-Pad21)") (class "Default")
      (node (ref "J3") (pin "21") (pinfunction "21_21") (pintype "passive"))
    )
    (net (code "156") (name "unconnected-(J3-Pad22)") (class "Default")
      (node (ref "J3") (pin "22") (pinfunction "22_22") (pintype "passive"))
    )
    (net (code "157") (name "unconnected-(J3-Pad23)") (class "Default")
      (node (ref "J3") (pin "23") (pinfunction "23_23") (pintype "passive"))
    )
    (net (code "158") (name "unconnected-(J3-Pad24)") (class "Default")
      (node (ref "J3") (pin "24") (pinfunction "24_24") (pintype "passive"))
    )
    (net (code "159") (name "unconnected-(J3-Pad25)") (class "Default")
      (node (ref "J3") (pin "25") (pinfunction "25_25") (pintype "passive"))
    )
    (net (code "160") (name "unconnected-(J3-Pad26)") (class "Default")
      (node (ref "J3") (pin "26") (pinfunction "26_26") (pintype "passive"))
    )
    (net (code "161") (name "unconnected-(J3-Pad27)") (class "Default")
      (node (ref "J3") (pin "27") (pinfunction "27_27") (pintype "passive"))
    )
    (net (code "162") (name "unconnected-(J3-Pad28)") (class "Default")
      (node (ref "J3") (pin "28") (pinfunction "28_28") (pintype "passive"))
    )
    (net (code "163") (name "unconnected-(J3-Pad30)") (class "Default")
      (node (ref "J3") (pin "30") (pinfunction "30_30") (pintype "passive"))
    )
    (net (code "164") (name "unconnected-(J3-Pad31)") (class "Default")
      (node (ref "J3") (pin "31") (pinfunction "31_31") (pintype "passive"))
    )
    (net (code "165") (name "unconnected-(J3-Pad34)") (class "Default")
      (node (ref "J3") (pin "34") (pinfunction "34_34") (pintype "passive"))
    )
    (net (code "166") (name "unconnected-(J3-Pad35)") (class "Default")
      (node (ref "J3") (pin "35") (pinfunction "35_35") (pintype "passive"))
    )
    (net (code "167") (name "unconnected-(J4-Pad5)") (class "Default")
      (node (ref "J4") (pin "5") (pinfunction "5_5") (pintype "passive"))
    )
    (net (code "168") (name "unconnected-(J4-Pad6)") (class "Default")
      (node (ref "J4") (pin "6") (pinfunction "6_6") (pintype "passive"))
    )
    (net (code "169") (name "unconnected-(J4-Pad7)") (class "Default")
      (node (ref "J4") (pin "7") (pinfunction "7_7") (pintype "passive"))
    )
    (net (code "170") (name "unconnected-(J4-Pad8)") (class "Default")
      (node (ref "J4") (pin "8") (pinfunction "8_8") (pintype "passive"))
    )
    (net (code "171") (name "unconnected-(J4-Pad9)") (class "Default")
      (node (ref "J4") (pin "9") (pinfunction "9_9") (pintype "passive"))
    )
    (net (code "172") (name "unconnected-(J4-Pad10)") (class "Default")
      (node (ref "J4") (pin "10") (pinfunction "10_10") (pintype "passive"))
    )
    (net (code "173") (name "unconnected-(J4-Pad11)") (class "Default")
      (node (ref "J4") (pin "11") (pinfunction "11_11") (pintype "passive"))
    )
    (net (code "174") (name "unconnected-(J4-Pad12)") (class "Default")
      (node (ref "J4") (pin "12") (pinfunction "12_12") (pintype "passive"))
    )
    (net (code "175") (name "unconnected-(J4-Pad13)") (class "Default")
      (node (ref "J4") (pin "13") (pinfunction "13_13") (pintype "passive"))
    )
    (net (code "176") (name "unconnected-(J4-Pad14)") (class "Default")
      (node (ref "J4") (pin "14") (pinfunction "14_14") (pintype "passive"))
    )
    (net (code "177") (name "unconnected-(J4-Pad15)") (class "Default")
      (node (ref "J4") (pin "15") (pinfunction "15_15") (pintype "passive"))
    )
    (net (code "178") (name "unconnected-(J4-Pad16)") (class "Default")
      (node (ref "J4") (pin "16") (pinfunction "16_16") (pintype "passive"))
    )
    (net (code "179") (name "unconnected-(J4-Pad17)") (class "Default")
      (node (ref "J4") (pin "17") (pinfunction "17_17") (pintype "passive"))
    )
    (net (code "180") (name "unconnected-(J4-Pad18)") (class "Default")
      (node (ref "J4") (pin "18") (pinfunction "18_18") (pintype "passive"))
    )
    (net (code "181") (name "unconnected-(J4-Pad19)") (class "Default")
      (node (ref "J4") (pin "19") (pinfunction "19_19") (pintype "passive"))
    )
    (net (code "182") (name "unconnected-(J4-Pad20)") (class "Default")
      (node (ref "J4") (pin "20") (pinfunction "20_20") (pintype "passive"))
    )
    (net (code "183") (name "unconnected-(J4-Pad21)") (class "Default")
      (node (ref "J4") (pin "21") (pinfunction "21_21") (pintype "passive"))
    )
    (net (code "184") (name "unconnected-(J4-Pad22)") (class "Default")
      (node (ref "J4") (pin "22") (pinfunction "22_22") (pintype "passive"))
    )
    (net (code "185") (name "unconnected-(J4-Pad23)") (class "Default")
      (node (ref "J4") (pin "23") (pinfunction "23_23") (pintype "passive"))
    )
    (net (code "186") (name "unconnected-(J4-Pad24)") (class "Default")
      (node (ref "J4") (pin "24") (pinfunction "24_24") (pintype "passive"))
    )
    (net (code "187") (name "unconnected-(J4-Pad25)") (class "Default")
      (node (ref "J4") (pin "25") (pinfunction "25_25") (pintype "passive"))
    )
    (net (code "188") (name "unconnected-(J4-Pad26)") (class "Default")
      (node (ref "J4") (pin "26") (pinfunction "26_26") (pintype "passive"))
    )
    (net (code "189") (name "unconnected-(J4-Pad27)") (class "Default")
      (node (ref "J4") (pin "27") (pinfunction "27_27") (pintype "passive"))
    )
    (net (code "190") (name "unconnected-(J4-Pad28)") (class "Default")
      (node (ref "J4") (pin "28") (pinfunction "28_28") (pintype "passive"))
    )
    (net (code "191") (name "unconnected-(J4-Pad30)") (class "Default")
      (node (ref "J4") (pin "30") (pinfunction "30_30") (pintype "passive"))
    )
    (net (code "192") (name "unconnected-(J4-Pad31)") (class "Default")
      (node (ref "J4") (pin "31") (pinfunction "31_31") (pintype "passive"))
    )
    (net (code "193") (name "unconnected-(J4-Pad34)") (class "Default")
      (node (ref "J4") (pin "34") (pinfunction "34_34") (pintype "passive"))
    )
    (net (code "194") (name "unconnected-(J4-Pad35)") (class "Default")
      (node (ref "J4") (pin "35") (pinfunction "35_35") (pintype "passive"))
    )
    (net (code "195") (name "unconnected-(J5-Pad5)") (class "Default")
      (node (ref "J5") (pin "5") (pinfunction "5_5") (pintype "passive"))
    )
    (net (code "196") (name "unconnected-(J5-Pad6)") (class "Default")
      (node (ref "J5") (pin "6") (pinfunction "6_6") (pintype "passive"))
    )
    (net (code "197") (name "unconnected-(J5-Pad7)") (class "Default")
      (node (ref "J5") (pin "7") (pinfunction "7_7") (pintype "passive"))
    )
    (net (code "198") (name "unconnected-(J5-Pad8)") (class "Default")
      (node (ref "J5") (pin "8") (pinfunction "8_8") (pintype "passive"))
    )
    (net (code "199") (name "unconnected-(J5-Pad9)") (class "Default")
      (node (ref "J5") (pin "9") (pinfunction "9_9") (pintype "passive"))
    )
    (net (code "200") (name "unconnected-(J5-Pad10)") (class "Default")
      (node (ref "J5") (pin "10") (pinfunction "10_10") (pintype "passive"))
    )
    (net (code "201") (name "unconnected-(J5-Pad11)") (class "Default")
      (node (ref "J5") (pin "11") (pinfunction "11_11") (pintype "passive"))
    )
    (net (code "202") (name "unconnected-(J5-Pad12)") (class "Default")
      (node (ref "J5") (pin "12") (pinfunction "12_12") (pintype "passive"))
    )
    (net (code "203") (name "unconnected-(J5-Pad13)") (class "Default")
      (node (ref "J5") (pin "13") (pinfunction "13_13") (pintype "passive"))
    )
    (net (code "204") (name "unconnected-(J5-Pad14)") (class "Default")
      (node (ref "J5") (pin "14") (pinfunction "14_14") (pintype "passive"))
    )
    (net (code "205") (name "unconnected-(J5-Pad15)") (class "Default")
      (node (ref "J5") (pin "15") (pinfunction "15_15") (pintype "passive"))
    )
    (net (code "206") (name "unconnected-(J5-Pad16)") (class "Default")
      (node (ref "J5") (pin "16") (pinfunction "16_16") (pintype "passive"))
    )
    (net (code "207") (name "unconnected-(J5-Pad17)") (class "Default")
      (node (ref "J5") (pin "17") (pinfunction "17_17") (pintype "passive"))
    )
    (net (code "208") (name "unconnected-(J5-Pad18)") (class "Default")
      (node (ref "J5") (pin "18") (pinfunction "18_18") (pintype "passive"))
    )
    (net (code "209") (name "unconnected-(J5-Pad19)") (class "Default")
      (node (ref "J5") (pin "19") (pinfunction "19_19") (pintype "passive"))
    )
    (net (code "210") (name "unconnected-(J5-Pad20)") (class "Default")
      (node (ref "J5") (pin "20") (pinfunction "20_20") (pintype "passive"))
    )
    (net (code "211") (name "unconnected-(J5-Pad21)") (class "Default")
      (node (ref "J5") (pin "21") (pinfunction "21_21") (pintype "passive"))
    )
    (net (code "212") (name "unconnected-(J5-Pad22)") (class "Default")
      (node (ref "J5") (pin "22") (pinfunction "22_22") (pintype "passive"))
    )
    (net (code "213") (name "unconnected-(J5-Pad23)") (class "Default")
      (node (ref "J5") (pin "23") (pinfunction "23_23") (pintype "passive"))
    )
    (net (code "214") (name "unconnected-(J5-Pad24)") (class "Default")
      (node (ref "J5") (pin "24") (pinfunction "24_24") (pintype "passive"))
    )
    (net (code "215") (name "unconnected-(J5-Pad25)") (class "Default")
      (node (ref "J5") (pin "25") (pinfunction "25_25") (pintype "passive"))
    )
    (net (code "216") (name "unconnected-(J5-Pad26)") (class "Default")
      (node (ref "J5") (pin "26") (pinfunction "26_26") (pintype "passive"))
    )
    (net (code "217") (name "unconnected-(J5-Pad27)") (class "Default")
      (node (ref "J5") (pin "27") (pinfunction "27_27") (pintype "passive"))
    )
    (net (code "218") (name "unconnected-(J5-Pad28)") (class "Default")
      (node (ref "J5") (pin "28") (pinfunction "28_28") (pintype "passive"))
    )
    (net (code "219") (name "unconnected-(J5-Pad30)") (class "Default")
      (node (ref "J5") (pin "30") (pinfunction "30_30") (pintype "passive"))
    )
    (net (code "220") (name "unconnected-(J5-Pad31)") (class "Default")
      (node (ref "J5") (pin "31") (pinfunction "31_31") (pintype "passive"))
    )
    (net (code "221") (name "unconnected-(J5-Pad34)") (class "Default")
      (node (ref "J5") (pin "34") (pinfunction "34_34") (pintype "passive"))
    )
    (net (code "222") (name "unconnected-(J5-Pad35)") (class "Default")
      (node (ref "J5") (pin "35") (pinfunction "35_35") (pintype "passive"))
    )
    (net (code "223") (name "unconnected-(J6-Pad5)") (class "Default")
      (node (ref "J6") (pin "5") (pinfunction "5_5") (pintype "passive"))
    )
    (net (code "224") (name "unconnected-(RPI-Pad2)") (class "Default")
      (node (ref "RPI") (pin "2") (pinfunction "2_2") (pintype "passive"))
    )
    (net (code "225") (name "unconnected-(RPI-Pad8)") (class "Default")
      (node (ref "RPI") (pin "8") (pinfunction "8_8") (pintype "passive"))
    )
    (net (code "226") (name "unconnected-(RPI-Pad11)") (class "Default")
      (node (ref "RPI") (pin "11") (pinfunction "11_11") (pintype "passive"))
    )
    (net (code "227") (name "unconnected-(RPI-Pad12)") (class "Default")
      (node (ref "RPI") (pin "12") (pinfunction "12_12") (pintype "passive"))
    )
    (net (code "228") (name "unconnected-(RPI-Pad14)") (class "Default")
      (node (ref "RPI") (pin "14") (pinfunction "14_14") (pintype "passive"))
    )
    (net (code "229") (name "unconnected-(RPI-Pad15)") (class "Default")
      (node (ref "RPI") (pin "15") (pinfunction "15_15") (pintype "passive"))
    )
    (net (code "230") (name "unconnected-(RPI-Pad16)") (class "Default")
      (node (ref "RPI") (pin "16") (pinfunction "16_16") (pintype "passive"))
    )
    (net (code "231") (name "unconnected-(RPI-Pad17)") (class "Default")
      (node (ref "RPI") (pin "17") (pinfunction "17_17") (pintype "passive"))
    )
    (net (code "232") (name "unconnected-(RPI-Pad18)") (class "Default")
      (node (ref "RPI") (pin "18") (pinfunction "18_18") (pintype "passive"))
    )
    (net (code "233") (name "unconnected-(RPI-Pad20)") (class "Default")
      (node (ref "RPI") (pin "20") (pinfunction "20_20") (pintype "passive"))
    )
    (net (code "234") (name "unconnected-(RPI-Pad21)") (class "Default")
      (node (ref "RPI") (pin "21") (pinfunction "21_21") (pintype "passive"))
    )
    (net (code "235") (name "unconnected-(RPI-Pad22)") (class "Default")
      (node (ref "RPI") (pin "22") (pinfunction "22_22") (pintype "passive"))
    )
    (net (code "236") (name "unconnected-(RPI-Pad23)") (class "Default")
      (node (ref "RPI") (pin "23") (pinfunction "23_23") (pintype "passive"))
    )
    (net (code "237") (name "unconnected-(RPI-Pad24)") (class "Default")
      (node (ref "RPI") (pin "24") (pinfunction "24_24") (pintype "passive"))
    )
    (net (code "238") (name "unconnected-(RPI-Pad25)") (class "Default")
      (node (ref "RPI") (pin "25") (pinfunction "25_25") (pintype "passive"))
    )
    (net (code "239") (name "unconnected-(RPI-Pad27)") (class "Default")
      (node (ref "RPI") (pin "27") (pinfunction "27_27") (pintype "passive"))
    )
    (net (code "240") (name "unconnected-(RPI-Pad28)") (class "Default")
      (node (ref "RPI") (pin "28") (pinfunction "28_28") (pintype "passive"))
    )
    (net (code "241") (name "unconnected-(RPI-Pad30)") (class "Default")
      (node (ref "RPI") (pin "30") (pinfunction "30_30") (pintype "passive"))
    )
    (net (code "242") (name "unconnected-(RPI-Pad31)") (class "Default")
      (node (ref "RPI") (pin "31") (pinfunction "31_31") (pintype "passive"))
    )
    (net (code "243") (name "unconnected-(RPI-Pad32)") (class "Default")
      (node (ref "RPI") (pin "32") (pinfunction "32_32") (pintype "passive"))
    )
    (net (code "244") (name "unconnected-(RPI-Pad34)") (class "Default")
      (node (ref "RPI") (pin "34") (pinfunction "34_34") (pintype "passive"))
    )
    (net (code "245") (name "unconnected-(RPI-Pad35)") (class "Default")
      (node (ref "RPI") (pin "35") (pinfunction "35_35") (pintype "passive"))
    )
    (net (code "246") (name "unconnected-(RPI-Pad36)") (class "Default")
      (node (ref "RPI") (pin "36") (pinfunction "36_36") (pintype "passive"))
    )
    (net (code "247") (name "unconnected-(RPI-Pad37)") (class "Default")
      (node (ref "RPI") (pin "37") (pinfunction "37_37") (pintype "passive"))
    )
    (net (code "248") (name "unconnected-(RPI-Pad38)") (class "Default")
      (node (ref "RPI") (pin "38") (pinfunction "38_38") (pintype "passive"))
    )
    (net (code "249") (name "unconnected-(RPI-Pad39)") (class "Default")
      (node (ref "RPI") (pin "39") (pinfunction "39_39") (pintype "passive"))
    )
    (net (code "250") (name "unconnected-(U4-NRST-Pad7)") (class "Default")
      (node (ref "U4") (pin "7") (pinfunction "NRST_7") (pintype "bidirectional"))
    )
    (net (code "251") (name "unconnected-(U4-PA1-Pad11)") (class "Default")
      (node (ref "U4") (pin "11") (pinfunction "PA1_11") (pintype "bidirectional"))
    )
    (net (code "252") (name "unconnected-(U4-PA2-Pad12)") (class "Default")
      (node (ref "U4") (pin "12") (pinfunction "PA2_12") (pintype "bidirectional"))
    )
    (net (code "253") (name "unconnected-(U4-PA3-Pad13)") (class "Default")
      (node (ref "U4") (pin "13") (pinfunction "PA3_13") (pintype "bidirectional"))
    )
    (net (code "254") (name "unconnected-(U4-PA8-Pad29)") (class "Default")
      (node (ref "U4") (pin "29") (pinfunction "PA8_29") (pintype "bidirectional"))
    )
    (net (code "255") (name "unconnected-(U4-PA11-Pad32)") (class "Default")
      (node (ref "U4") (pin "32") (pinfunction "PA11_32") (pintype "bidirectional"))
    )
    (net (code "256") (name "unconnected-(U4-PA12-Pad33)") (class "Default")
      (node (ref "U4") (pin "33") (pinfunction "PA12_33") (pintype "bidirectional"))
    )
    (net (code "257") (name "unconnected-(U4-PA15-Pad38)") (class "Default")
      (node (ref "U4") (pin "38") (pinfunction "PA15_38") (pintype "bidirectional"))
    )
    (net (code "258") (name "unconnected-(U4-PB12-Pad25)") (class "Default")
      (node (ref "U4") (pin "25") (pinfunction "PB12_25") (pintype "bidirectional"))
    )
    (net (code "259") (name "unconnected-(U4-PB13-Pad26)") (class "Default")
      (node (ref "U4") (pin "26") (pinfunction "PB13_26") (pintype "bidirectional"))
    )
    (net (code "260") (name "unconnected-(U4-PB14-Pad27)") (class "Default")
      (node (ref "U4") (pin "27") (pinfunction "PB14_27") (pintype "bidirectional"))
    )
    (net (code "261") (name "unconnected-(U4-PB15-Pad28)") (class "Default")
      (node (ref "U4") (pin "28") (pinfunction "PB15_28") (pintype "bidirectional"))
    )
    (net (code "262") (name "unconnected-(U4-PC13-Pad2)") (class "Default")
      (node (ref "U4") (pin "2") (pinfunction "PC13_2") (pintype "bidirectional"))
    )
    (net (code "263") (name "unconnected-(U4-PC14-OSC32_IN(PC14)-Pad3)") (class "Default")
      (node (ref "U4") (pin "3") (pinfunction "PC14-OSC32_IN(PC14)_3") (pintype "bidirectional"))
    )
    (net (code "264") (name "unconnected-(U4-PC15-OSC32_OUT(PC15)-Pad4)") (class "Default")
      (node (ref "U4") (pin "4") (pinfunction "PC15-OSC32_OUT(PC15)_4") (pintype "bidirectional"))
    )
    (net (code "265") (name "unconnected-(U5-IO34-Pad6)") (class "Default")
      (node (ref "U5") (pin "6") (pinfunction "IO34_6") (pintype "input+no_connect"))
    )
    (net (code "266") (name "unconnected-(U5-IO35-Pad7)") (class "Default")
      (node (ref "U5") (pin "7") (pinfunction "IO35_7") (pintype "input+no_connect"))
    )
    (net (code "267") (name "unconnected-(U5-SCL{slash}CLK-Pad20)") (class "Default")
      (node (ref "U5") (pin "20") (pinfunction "SCL/CLK_20") (pintype "bidirectional"))
    )
    (net (code "268") (name "unconnected-(U5-SCS{slash}CMD-Pad19)") (class "Default")
      (node (ref "U5") (pin "19") (pinfunction "SCS/CMD_19") (pintype "bidirectional"))
    )
    (net (code "269") (name "unconnected-(U5-SD1{slash}SD1-Pad22)") (class "Default")
      (node (ref "U5") (pin "22") (pinfunction "SD1/SD1_22") (pintype "bidirectional"))
    )
    (net (code "270") (name "unconnected-(U5-SDO{slash}SD0-Pad21)") (class "Default")
      (node (ref "U5") (pin "21") (pinfunction "SDO/SD0_21") (pintype "bidirectional"))
    )
    (net (code "271") (name "unconnected-(U5-SENSOR_VN-Pad5)") (class "Default")
      (node (ref "U5") (pin "5") (pinfunction "SENSOR_VN_5") (pintype "input+no_connect"))
    )
    (net (code "272") (name "unconnected-(U5-SENSOR_VP-Pad4)") (class "Default")
      (node (ref "U5") (pin "4") (pinfunction "SENSOR_VP_4") (pintype "input+no_connect"))
    )
    (net (code "273") (name "unconnected-(U5-SHD{slash}SD2-Pad17)") (class "Default")
      (node (ref "U5") (pin "17") (pinfunction "SHD/SD2_17") (pintype "bidirectional"))
    )
    (net (code "274") (name "unconnected-(U5-SWP{slash}SD3-Pad18)") (class "Default")
      (node (ref "U5") (pin "18") (pinfunction "SWP/SD3_18") (pintype "bidirectional"))
    )
    (net (code "275") (name "unconnected-(U6-DEN_A{slash}G-Pad13)") (class "Default")
      (node (ref "U6") (pin "13") (pinfunction "DEN_A/G_13") (pintype "output"))
    )
    (net (code "276") (name "unconnected-(U6-DRDY_M-Pad9)") (class "Default")
      (node (ref "U6") (pin "9") (pinfunction "DRDY_M_9") (pintype "output"))
    )
    (net (code "277") (name "unconnected-(U6-INT1_A{slash}G-Pad11)") (class "Default")
      (node (ref "U6") (pin "11") (pinfunction "INT1_A/G_11") (pintype "output"))
    )
    (net (code "278") (name "unconnected-(U6-INT2_A{slash}G-Pad12)") (class "Default")
      (node (ref "U6") (pin "12") (pinfunction "INT2_A/G_12") (pintype "output"))
    )
    (net (code "279") (name "unconnected-(U6-INT_M-Pad10)") (class "Default")
      (node (ref "U6") (pin "10") (pinfunction "INT_M_10") (pintype "output"))
    )
  )
)
